# harp_behavior.net
KiCad netlist of a schematic drawn in EAGLE
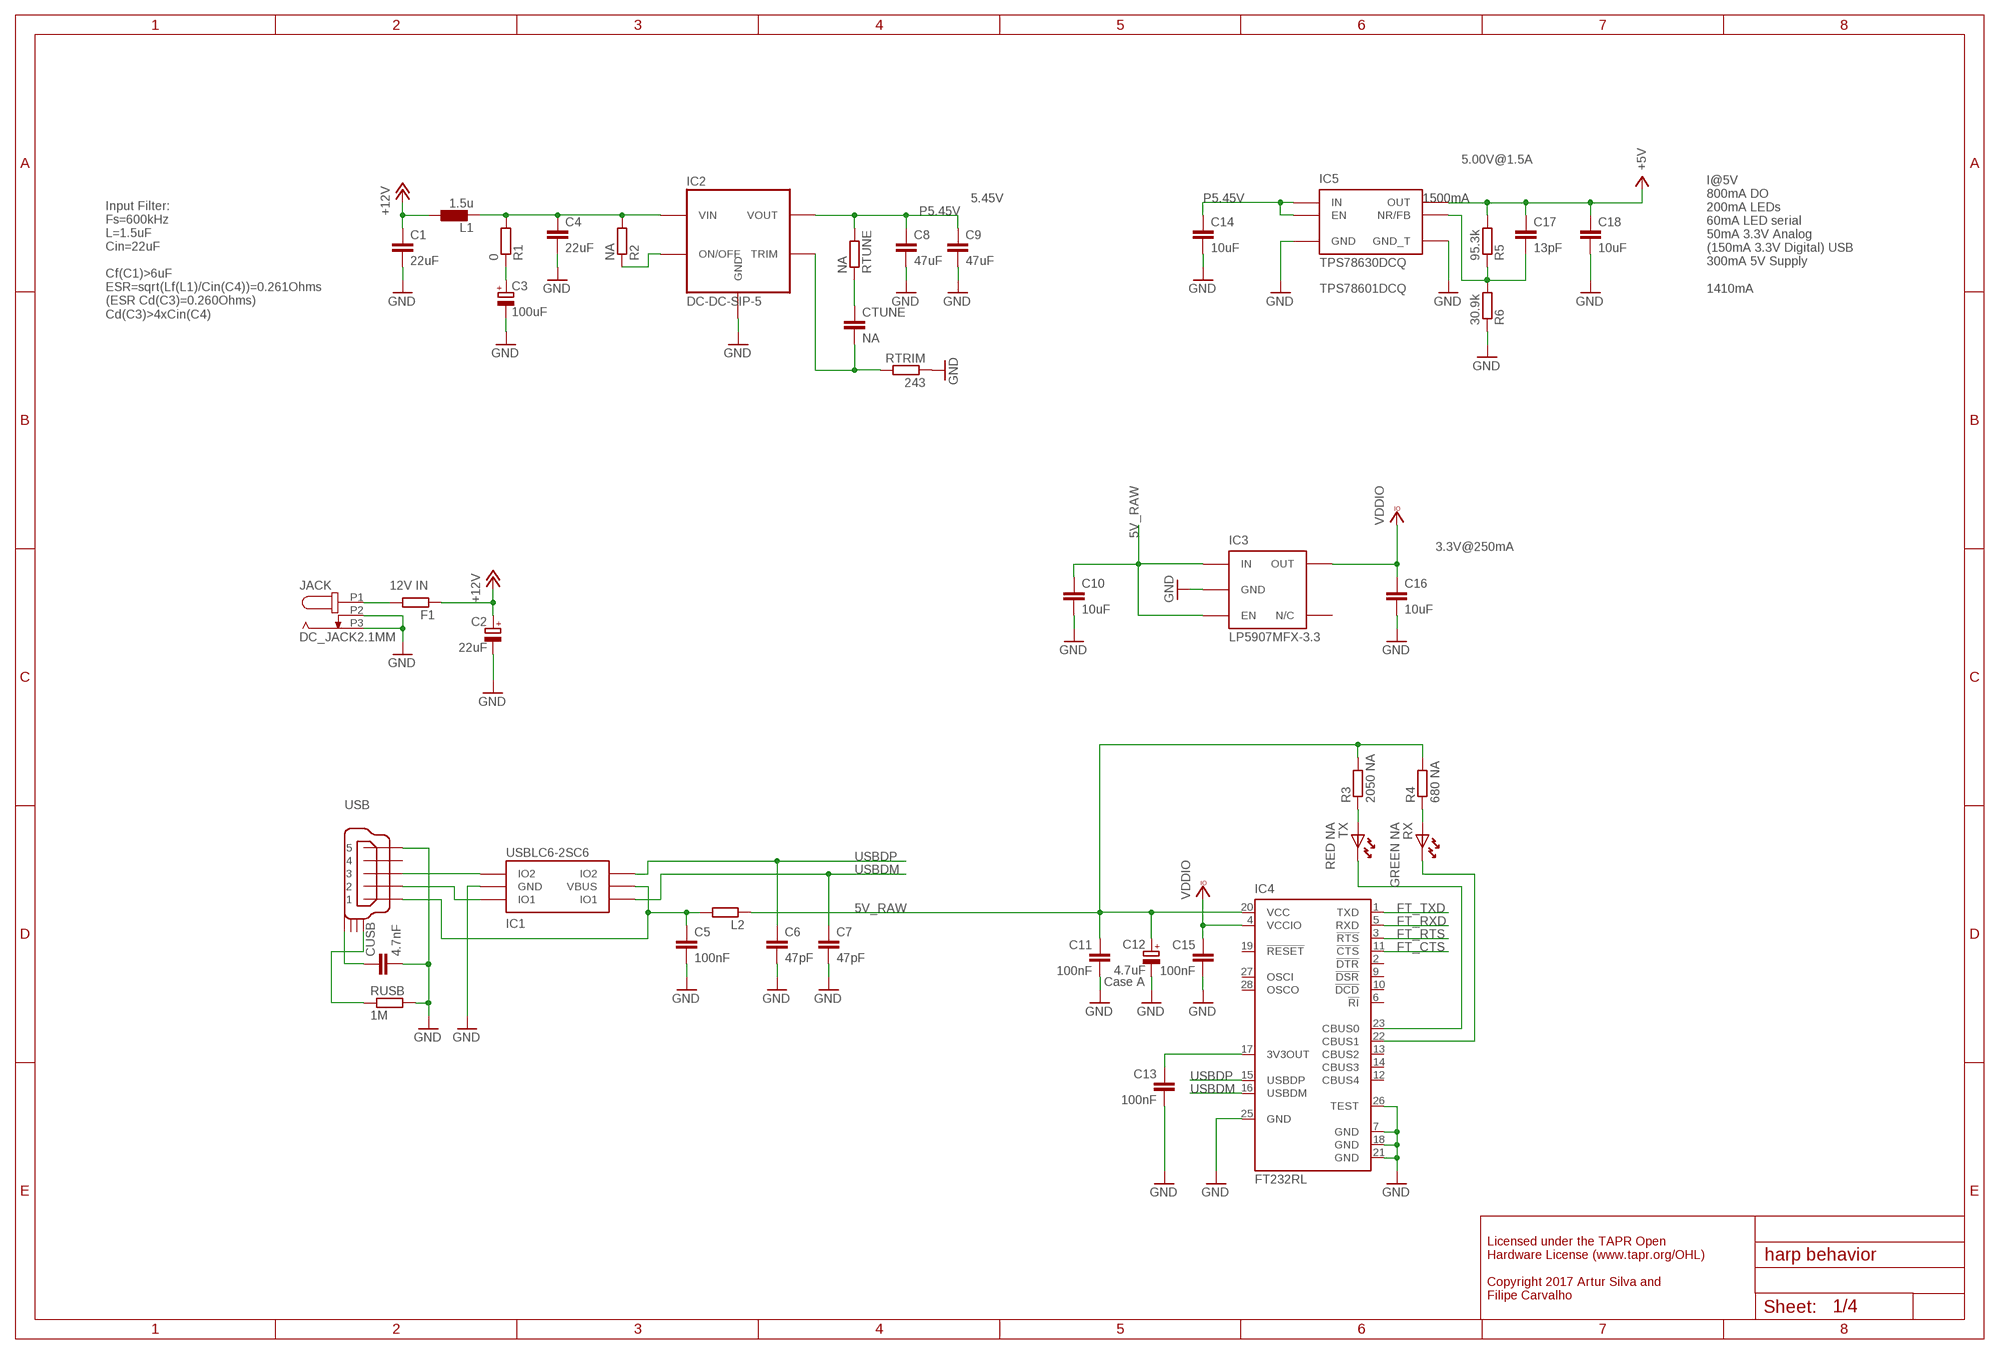
[diagram p0: schematic, sheet 1]
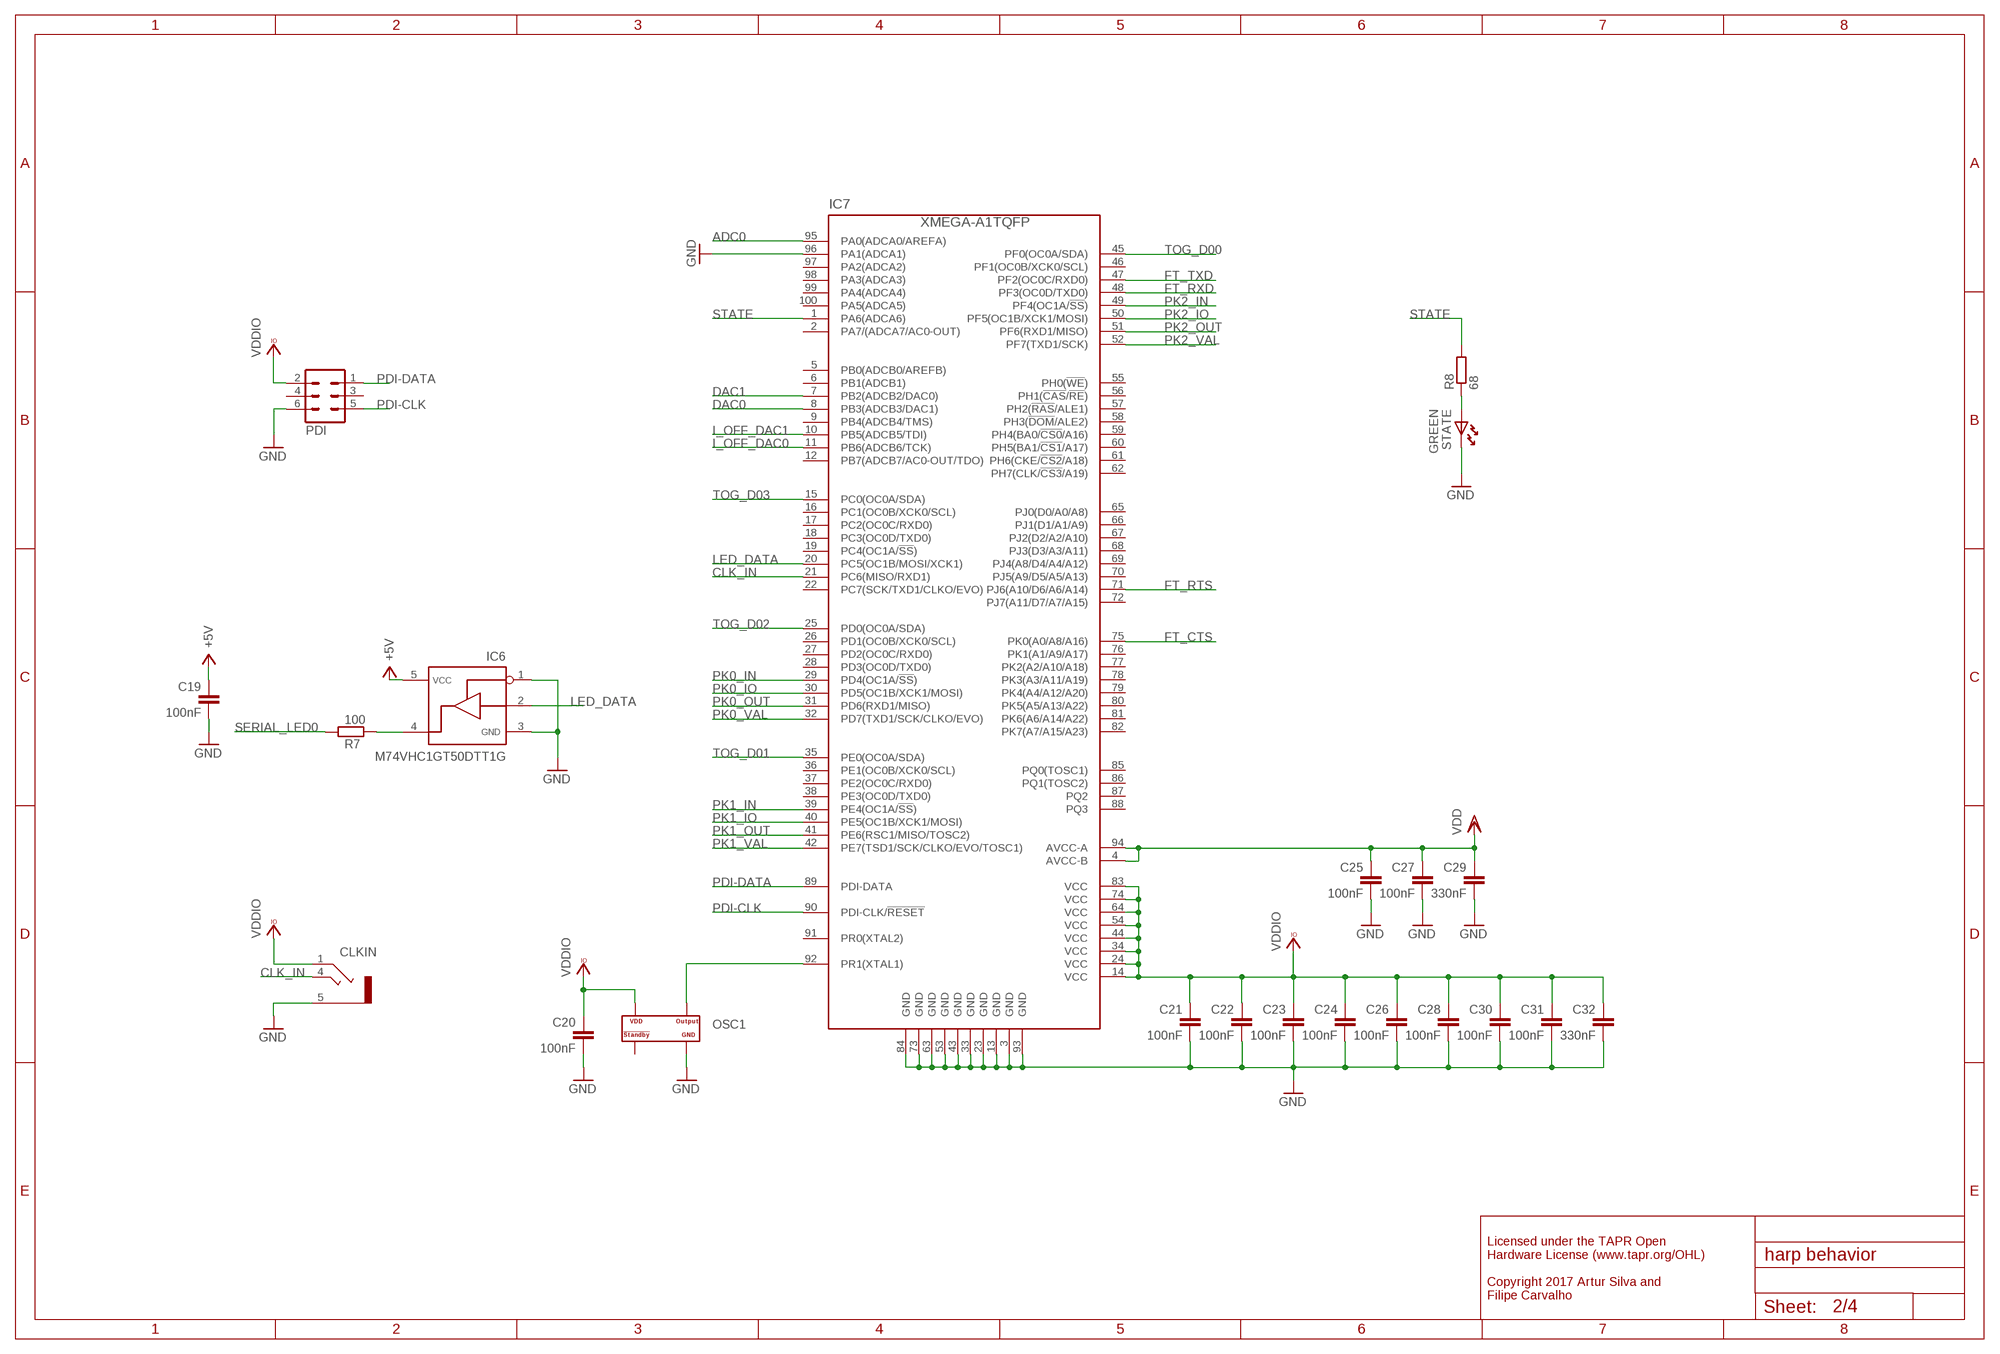
[diagram p1: schematic, sheet 2]
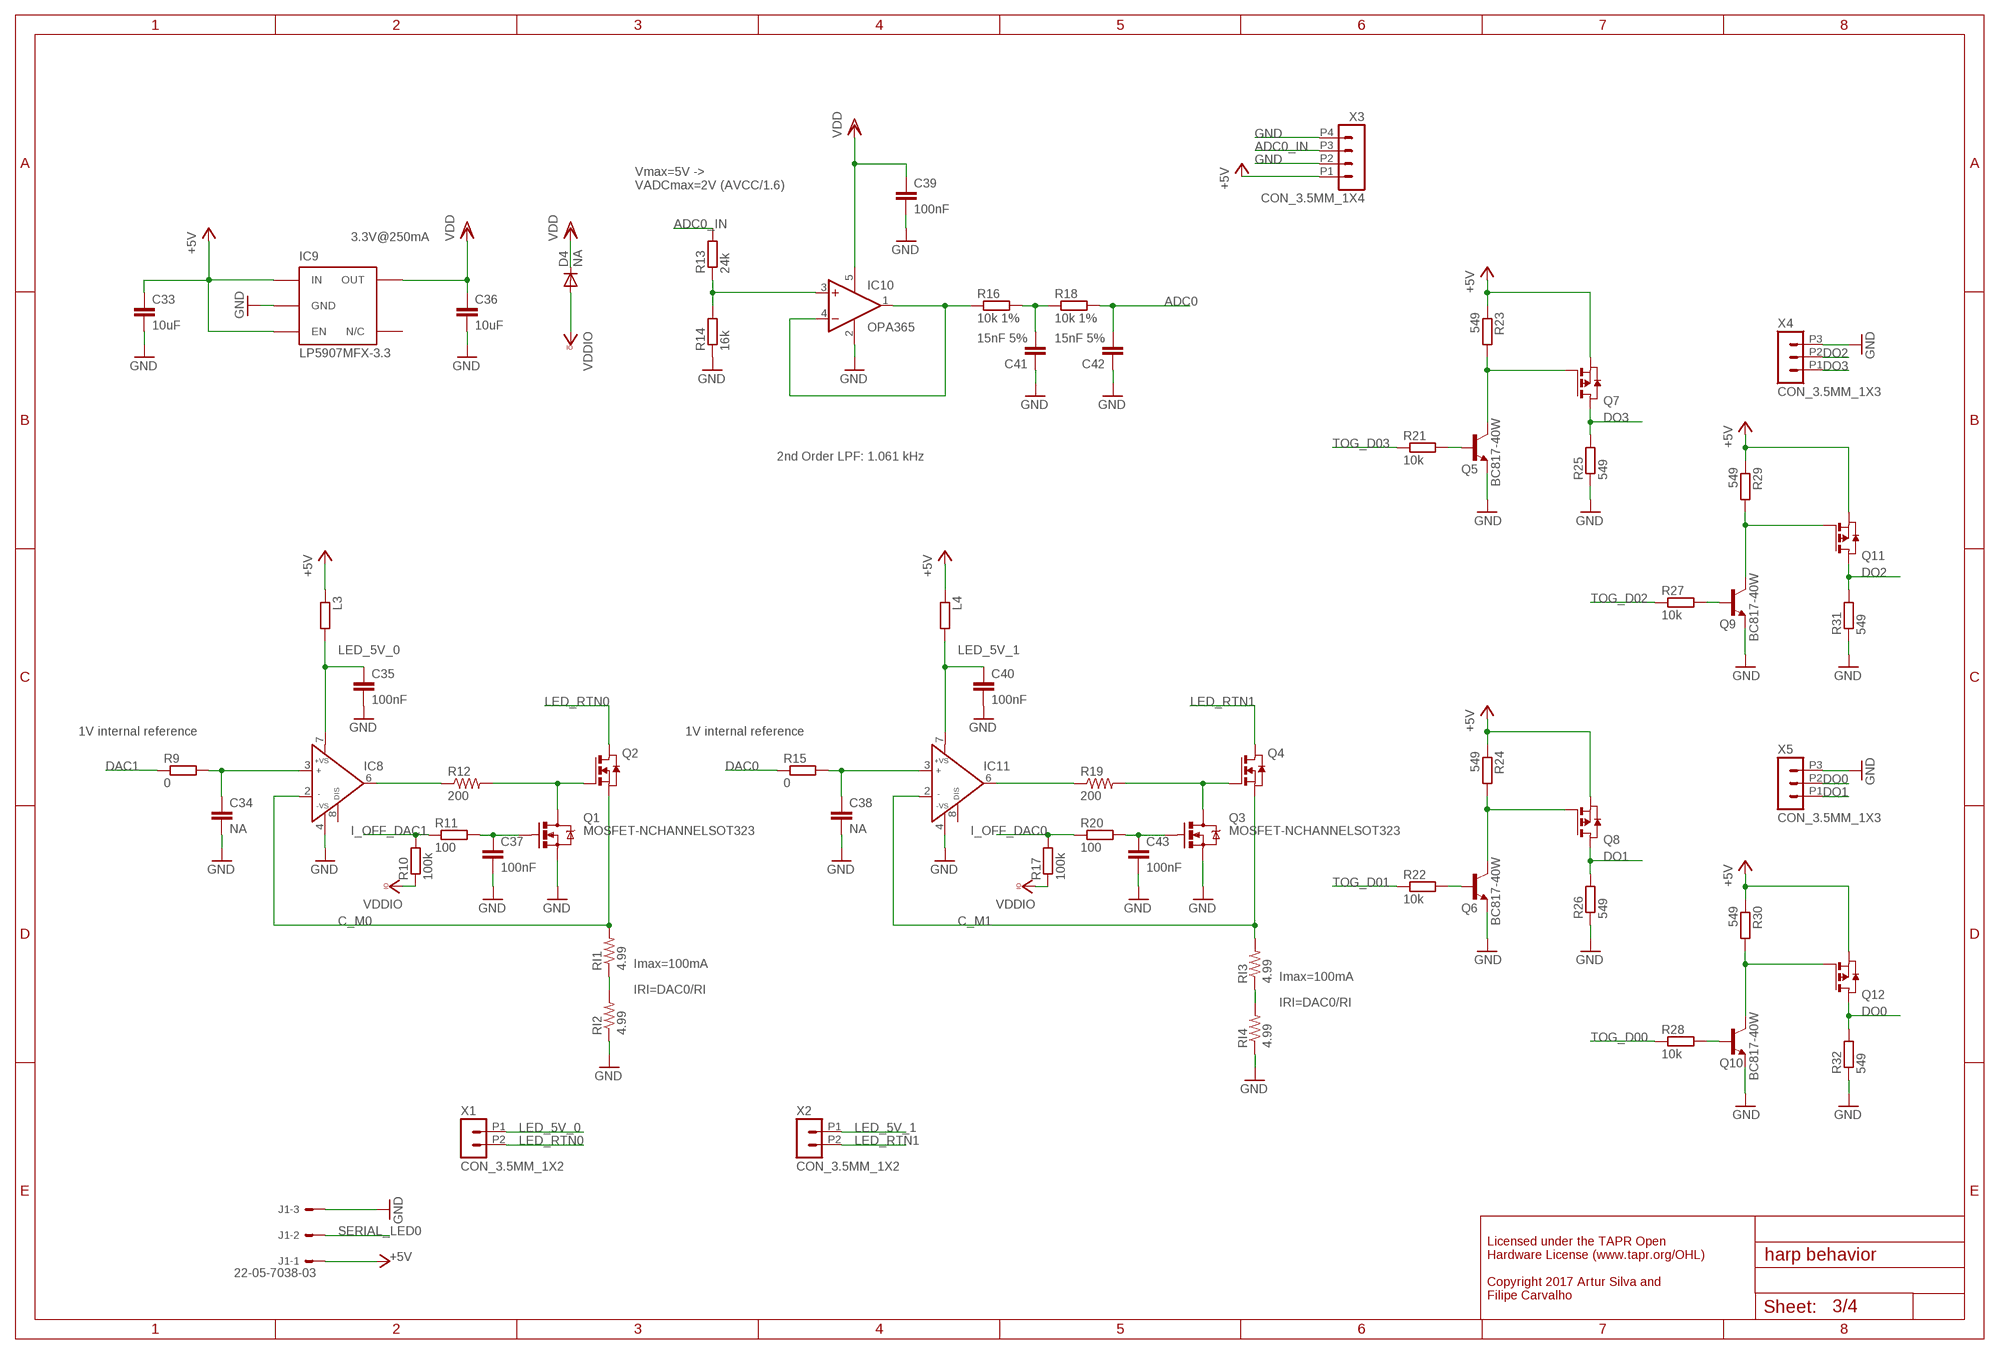
[diagram p2: schematic, sheet 3]
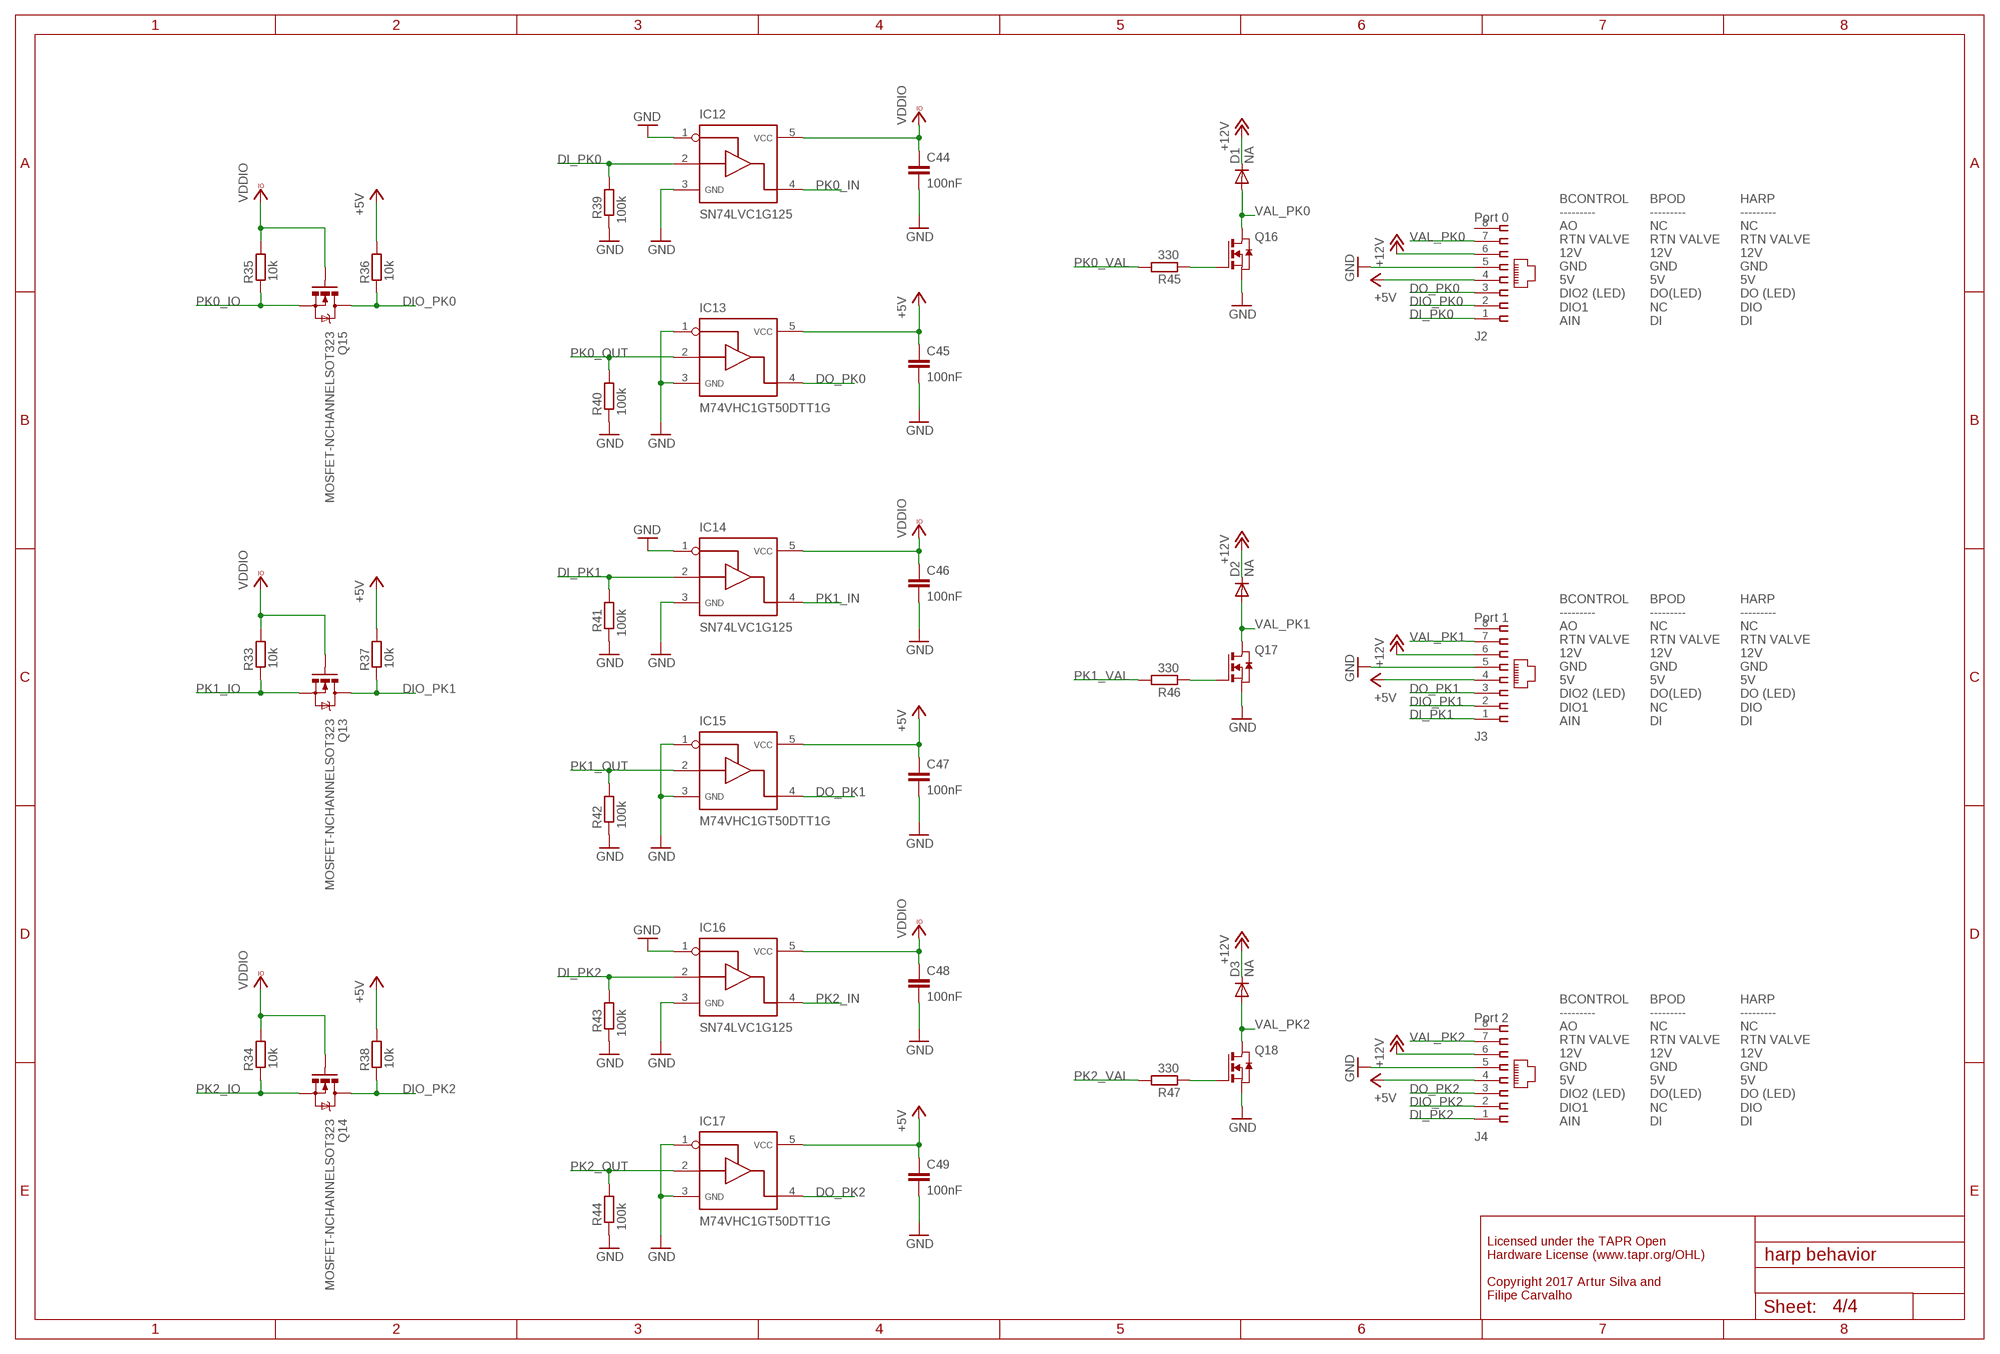
[diagram p3: schematic, sheet 4]

(export (version "E")
  (design (tool "Eeschema 10.0.6"))
  (components
    (comp (ref "C1")
      (value "22uF")
      (footprint "eagle-import:C1210")
      (libsource (lib "eagle-import") (part "C-EUC1210"))
    )
    (comp (ref "C2")
      (value "22uF")
      (footprint "eagle-import:CAP_100UF_HAND")
      (libsource (lib "eagle-import") (part "CAP_100UFHAND"))
    )
    (comp (ref "C3")
      (value "100uF")
      (footprint "eagle-import:PANASONIC_E")
      (libsource (lib "eagle-import") (part "CPOL-EUE"))
    )
    (comp (ref "C4")
      (value "22uF")
      (footprint "eagle-import:C1210")
      (libsource (lib "eagle-import") (part "C-EUC1210"))
    )
    (comp (ref "C5")
      (value "100nF")
      (footprint "eagle-import:C0402")
      (libsource (lib "eagle-import") (part "C-EUC0402"))
    )
    (comp (ref "C6")
      (value "47pF")
      (footprint "eagle-import:C0402")
      (libsource (lib "eagle-import") (part "C-EUC0402"))
    )
    (comp (ref "C7")
      (value "47pF")
      (footprint "eagle-import:C0402")
      (libsource (lib "eagle-import") (part "C-EUC0402"))
    )
    (comp (ref "C8")
      (value "47uF")
      (footprint "eagle-import:C1210")
      (libsource (lib "eagle-import") (part "C-EUC1210"))
    )
    (comp (ref "C9")
      (value "47uF")
      (footprint "eagle-import:C1210")
      (libsource (lib "eagle-import") (part "C-EUC1210"))
    )
    (comp (ref "C10")
      (value "10uF")
      (footprint "eagle-import:C0603")
      (libsource (lib "eagle-import") (part "C-EUC0603"))
    )
    (comp (ref "C11")
      (value "100nF")
      (footprint "eagle-import:C0402")
      (libsource (lib "eagle-import") (part "C-EUC0402"))
    )
    (comp (ref "C12")
      (value "4.7uF")
      (footprint "eagle-import:A_3216-18W")
      (libsource (lib "eagle-import") (part "CPOL-EUA/3216-18W"))
    )
    (comp (ref "C13")
      (value "100nF")
      (footprint "eagle-import:C0402")
      (libsource (lib "eagle-import") (part "C-EUC0402"))
    )
    (comp (ref "C14")
      (value "10uF")
      (footprint "eagle-import:C0603")
      (libsource (lib "eagle-import") (part "C-EUC0603"))
    )
    (comp (ref "C15")
      (value "100nF")
      (footprint "eagle-import:C0402")
      (libsource (lib "eagle-import") (part "C-EUC0402"))
    )
    (comp (ref "C16")
      (value "10uF")
      (footprint "eagle-import:C0603")
      (libsource (lib "eagle-import") (part "C-EUC0603"))
    )
    (comp (ref "C17")
      (value "13pF")
      (footprint "eagle-import:C0402")
      (libsource (lib "eagle-import") (part "C-EUC0402"))
    )
    (comp (ref "C18")
      (value "10uF")
      (footprint "eagle-import:C0603")
      (libsource (lib "eagle-import") (part "C-EUC0603"))
    )
    (comp (ref "CTUNE")
      (value "NA")
      (footprint "eagle-import:C0402")
      (libsource (lib "eagle-import") (part "C-EUC0402"))
    )
    (comp (ref "CUSB")
      (value "4.7nF")
      (footprint "eagle-import:C0402")
      (libsource (lib "eagle-import") (part "C-EUC0402"))
    )
    (comp (ref "F1")
      (value "1A FB")
      (footprint "eagle-import:R0603")
      (libsource (lib "eagle-import") (part "R-EU_R0603"))
    )
    (comp (ref "IC1")
      (value "USBLC6-2SC6")
      (footprint "eagle-import:SOT23-6L")
      (libsource (lib "eagle-import") (part "USBLC6-2"))
    )
    (comp (ref "IC2")
      (value "DC-DC-SIP-5")
      (footprint "eagle-import:SIP-5")
      (libsource (lib "eagle-import") (part "DC-DC-SIP-5"))
    )
    (comp (ref "IC3")
      (value "LP5907MFX-3.3")
      (footprint "eagle-import:TSOT23-5")
      (libsource (lib "eagle-import") (part "TLV700XX"))
    )
    (comp (ref "IC4")
      (value "FT232RL")
      (footprint "eagle-import:SSOP28")
      (libsource (lib "eagle-import") (part "FT232RL"))
    )
    (comp (ref "IC5")
      (value "TPS78630DCQ")
      (footprint "eagle-import:SOT223-6")
      (libsource (lib "eagle-import") (part "TPS795XX"))
    )
    (comp (ref "JACK")
      (value "DC_JACK2.1MM")
      (footprint "eagle-import:DC_POWER_INPUT_2.1MM")
      (libsource (lib "eagle-import") (part "DC_JACK2.1MM"))
    )
    (comp (ref "L1")
      (value "1.5u")
      (footprint "eagle-import:IND_LPS4012")
      (libsource (lib "eagle-import") (part "INDLPS4012"))
    )
    (comp (ref "L2")
      (value "???")
      (footprint "eagle-import:R0805")
      (libsource (lib "eagle-import") (part "R-EU_R0805"))
    )
    (comp (ref "R1")
      (value "0")
      (footprint "eagle-import:R0402")
      (libsource (lib "eagle-import") (part "R-EU_R0402"))
    )
    (comp (ref "R2")
      (value "NA")
      (footprint "eagle-import:R0402")
      (libsource (lib "eagle-import") (part "R-EU_R0402"))
    )
    (comp (ref "R3")
      (value "2050 NA")
      (footprint "eagle-import:R0402")
      (libsource (lib "eagle-import") (part "R-EU_R0402"))
    )
    (comp (ref "R4")
      (value "680 NA")
      (footprint "eagle-import:R0402")
      (libsource (lib "eagle-import") (part "R-EU_R0402"))
    )
    (comp (ref "R5")
      (value "95.3k")
      (footprint "eagle-import:R0402")
      (libsource (lib "eagle-import") (part "R-EU_R0402"))
    )
    (comp (ref "R6")
      (value "30.9k")
      (footprint "eagle-import:R0402")
      (libsource (lib "eagle-import") (part "R-EU_R0402"))
    )
    (comp (ref "RTRIM")
      (value "243")
      (footprint "eagle-import:R0402")
      (libsource (lib "eagle-import") (part "R-EU_R0402"))
    )
    (comp (ref "RTUNE")
      (value "NA")
      (footprint "eagle-import:R0402")
      (libsource (lib "eagle-import") (part "R-EU_R0402"))
    )
    (comp (ref "RUSB")
      (value "1M")
      (footprint "eagle-import:R0402")
      (libsource (lib "eagle-import") (part "R-EU_R0402"))
    )
    (comp (ref "RX")
      (value "GREEN NA")
      (footprint "eagle-import:LED_HAND")
      (libsource (lib "eagle-import") (part "LEDHAND"))
    )
    (comp (ref "TX")
      (value "RED NA")
      (footprint "eagle-import:LED_HAND")
      (libsource (lib "eagle-import") (part "LEDHAND"))
    )
    (comp (ref "USB")
      (value "USB_MINI_B")
      (footprint "eagle-import:240-0002-1")
      (libsource (lib "eagle-import") (part "USB_MINI_B"))
    )
    (comp (ref "C19")
      (value "100nF")
      (footprint "eagle-import:C0402")
      (libsource (lib "eagle-import") (part "C-EUC0402"))
    )
    (comp (ref "C20")
      (value "100nF")
      (footprint "eagle-import:C0402")
      (libsource (lib "eagle-import") (part "C-EUC0402"))
    )
    (comp (ref "C21")
      (value "100nF")
      (footprint "eagle-import:C0402")
      (libsource (lib "eagle-import") (part "C-EUC0402"))
    )
    (comp (ref "C22")
      (value "100nF")
      (footprint "eagle-import:C0402")
      (libsource (lib "eagle-import") (part "C-EUC0402"))
    )
    (comp (ref "C23")
      (value "100nF")
      (footprint "eagle-import:C0402")
      (libsource (lib "eagle-import") (part "C-EUC0402"))
    )
    (comp (ref "C24")
      (value "100nF")
      (footprint "eagle-import:C0402")
      (libsource (lib "eagle-import") (part "C-EUC0402"))
    )
    (comp (ref "C25")
      (value "100nF")
      (footprint "eagle-import:C0402")
      (libsource (lib "eagle-import") (part "C-EUC0402"))
    )
    (comp (ref "C26")
      (value "100nF")
      (footprint "eagle-import:C0402")
      (libsource (lib "eagle-import") (part "C-EUC0402"))
    )
    (comp (ref "C27")
      (value "100nF")
      (footprint "eagle-import:C0402")
      (libsource (lib "eagle-import") (part "C-EUC0402"))
    )
    (comp (ref "C28")
      (value "100nF")
      (footprint "eagle-import:C0402")
      (libsource (lib "eagle-import") (part "C-EUC0402"))
    )
    (comp (ref "C29")
      (value "330nF")
      (footprint "eagle-import:C0402")
      (libsource (lib "eagle-import") (part "C-EUC0402"))
    )
    (comp (ref "C30")
      (value "100nF")
      (footprint "eagle-import:C0402")
      (libsource (lib "eagle-import") (part "C-EUC0402"))
    )
    (comp (ref "C31")
      (value "100nF")
      (footprint "eagle-import:C0402")
      (libsource (lib "eagle-import") (part "C-EUC0402"))
    )
    (comp (ref "C32")
      (value "330nF")
      (footprint "eagle-import:C0402")
      (libsource (lib "eagle-import") (part "C-EUC0402"))
    )
    (comp (ref "CLKIN")
      (value "STEREO_JACK")
      (footprint "eagle-import:35RASMT2BHNTRX")
      (libsource (lib "eagle-import") (part "STEREO_JACK"))
    )
    (comp (ref "IC6")
      (value "M74VHC1GT50DTT1G")
      (footprint "eagle-import:SOT23-5")
      (libsource (lib "eagle-import") (part "SN74LVC1G125"))
    )
    (comp (ref "IC7")
      (value "XMEGA-A1TQFP")
      (footprint "eagle-import:TQFP100")
      (libsource (lib "eagle-import") (part "XMEGA-A1TQFP"))
    )
    (comp (ref "OSC1")
      (value "OSCILLATOR")
      (footprint "eagle-import:OSCILLATOR_3.2X2.5")
      (libsource (lib "eagle-import") (part "OSCILLATOR"))
    )
    (comp (ref "PDI")
      (value "MA03-2")
      (footprint "eagle-import:MA03-2")
      (libsource (lib "eagle-import") (part "MA03-2"))
    )
    (comp (ref "R7")
      (value "100")
      (footprint "eagle-import:R0402")
      (libsource (lib "eagle-import") (part "R-EU_R0402"))
    )
    (comp (ref "R8")
      (value "68")
      (footprint "eagle-import:R0402")
      (libsource (lib "eagle-import") (part "R-EU_R0402"))
    )
    (comp (ref "STATE")
      (value "GREEN")
      (footprint "eagle-import:LED_HAND")
      (libsource (lib "eagle-import") (part "LEDHAND"))
    )
    (comp (ref "C44")
      (value "100nF")
      (footprint "eagle-import:C0402")
      (libsource (lib "eagle-import") (part "C-EUC0402"))
    )
    (comp (ref "C45")
      (value "100nF")
      (footprint "eagle-import:C0402")
      (libsource (lib "eagle-import") (part "C-EUC0402"))
    )
    (comp (ref "C46")
      (value "100nF")
      (footprint "eagle-import:C0402")
      (libsource (lib "eagle-import") (part "C-EUC0402"))
    )
    (comp (ref "C47")
      (value "100nF")
      (footprint "eagle-import:C0402")
      (libsource (lib "eagle-import") (part "C-EUC0402"))
    )
    (comp (ref "C48")
      (value "100nF")
      (footprint "eagle-import:C0402")
      (libsource (lib "eagle-import") (part "C-EUC0402"))
    )
    (comp (ref "C49")
      (value "100nF")
      (footprint "eagle-import:C0402")
      (libsource (lib "eagle-import") (part "C-EUC0402"))
    )
    (comp (ref "D1")
      (value "NA")
      (footprint "eagle-import:SOD323-R")
      (libsource (lib "eagle-import") (part "DIODE-SOD323-R"))
    )
    (comp (ref "D2")
      (value "NA")
      (footprint "eagle-import:SOD323-R")
      (libsource (lib "eagle-import") (part "DIODE-SOD323-R"))
    )
    (comp (ref "D3")
      (value "NA")
      (footprint "eagle-import:SOD323-R")
      (libsource (lib "eagle-import") (part "DIODE-SOD323-R"))
    )
    (comp (ref "IC12")
      (value "SN74LVC1G125")
      (footprint "eagle-import:SOT23-5")
      (libsource (lib "eagle-import") (part "SN74LVC1G125"))
    )
    (comp (ref "IC13")
      (value "M74VHC1GT50DTT1G")
      (footprint "eagle-import:SOT23-5")
      (libsource (lib "eagle-import") (part "SN74LVC1G125"))
    )
    (comp (ref "IC14")
      (value "SN74LVC1G125")
      (footprint "eagle-import:SOT23-5")
      (libsource (lib "eagle-import") (part "SN74LVC1G125"))
    )
    (comp (ref "IC15")
      (value "M74VHC1GT50DTT1G")
      (footprint "eagle-import:SOT23-5")
      (libsource (lib "eagle-import") (part "SN74LVC1G125"))
    )
    (comp (ref "IC16")
      (value "SN74LVC1G125")
      (footprint "eagle-import:SOT23-5")
      (libsource (lib "eagle-import") (part "SN74LVC1G125"))
    )
    (comp (ref "IC17")
      (value "M74VHC1GT50DTT1G")
      (footprint "eagle-import:SOT23-5")
      (libsource (lib "eagle-import") (part "SN74LVC1G125"))
    )
    (comp (ref "J2")
      (value "Port 0")
      (footprint "eagle-import:520426-4")
      (libsource (lib "eagle-import") (part "520426-4"))
    )
    (comp (ref "J3")
      (value "Port 1")
      (footprint "eagle-import:520426-4")
      (libsource (lib "eagle-import") (part "520426-4"))
    )
    (comp (ref "J4")
      (value "Port 2")
      (footprint "eagle-import:520426-4")
      (libsource (lib "eagle-import") (part "520426-4"))
    )
    (comp (ref "Q13")
      (value "MOSFET-NCHANNELSOT323")
      (footprint "eagle-import:SOT323")
      (libsource (lib "eagle-import") (part "MOSFET-NCHANNELSOT323"))
    )
    (comp (ref "Q14")
      (value "MOSFET-NCHANNELSOT323")
      (footprint "eagle-import:SOT323")
      (libsource (lib "eagle-import") (part "MOSFET-NCHANNELSOT323"))
    )
    (comp (ref "Q15")
      (value "MOSFET-NCHANNELSOT323")
      (footprint "eagle-import:SOT323")
      (libsource (lib "eagle-import") (part "MOSFET-NCHANNELSOT323"))
    )
    (comp (ref "Q16")
      (value "NMOSSOT223")
      (footprint "eagle-import:SOT223")
      (libsource (lib "eagle-import") (part "NMOSSOT223"))
    )
    (comp (ref "Q17")
      (value "NMOSSOT223")
      (footprint "eagle-import:SOT223")
      (libsource (lib "eagle-import") (part "NMOSSOT223"))
    )
    (comp (ref "Q18")
      (value "NMOSSOT223")
      (footprint "eagle-import:SOT223")
      (libsource (lib "eagle-import") (part "NMOSSOT223"))
    )
    (comp (ref "R33")
      (value "10k")
      (footprint "eagle-import:R0402")
      (libsource (lib "eagle-import") (part "R-EU_R0402"))
    )
    (comp (ref "R34")
      (value "10k")
      (footprint "eagle-import:R0402")
      (libsource (lib "eagle-import") (part "R-EU_R0402"))
    )
    (comp (ref "R35")
      (value "10k")
      (footprint "eagle-import:R0402")
      (libsource (lib "eagle-import") (part "R-EU_R0402"))
    )
    (comp (ref "R36")
      (value "10k")
      (footprint "eagle-import:R0402")
      (libsource (lib "eagle-import") (part "R-EU_R0402"))
    )
    (comp (ref "R37")
      (value "10k")
      (footprint "eagle-import:R0402")
      (libsource (lib "eagle-import") (part "R-EU_R0402"))
    )
    (comp (ref "R38")
      (value "10k")
      (footprint "eagle-import:R0402")
      (libsource (lib "eagle-import") (part "R-EU_R0402"))
    )
    (comp (ref "R39")
      (value "100k")
      (footprint "eagle-import:R0402")
      (libsource (lib "eagle-import") (part "R-EU_R0402"))
    )
    (comp (ref "R40")
      (value "100k")
      (footprint "eagle-import:R0402")
      (libsource (lib "eagle-import") (part "R-EU_R0402"))
    )
    (comp (ref "R41")
      (value "100k")
      (footprint "eagle-import:R0402")
      (libsource (lib "eagle-import") (part "R-EU_R0402"))
    )
    (comp (ref "R42")
      (value "100k")
      (footprint "eagle-import:R0402")
      (libsource (lib "eagle-import") (part "R-EU_R0402"))
    )
    (comp (ref "R43")
      (value "100k")
      (footprint "eagle-import:R0402")
      (libsource (lib "eagle-import") (part "R-EU_R0402"))
    )
    (comp (ref "R44")
      (value "100k")
      (footprint "eagle-import:R0402")
      (libsource (lib "eagle-import") (part "R-EU_R0402"))
    )
    (comp (ref "R45")
      (value "330")
      (footprint "eagle-import:R0402")
      (libsource (lib "eagle-import") (part "R-EU_R0402"))
    )
    (comp (ref "R46")
      (value "330")
      (footprint "eagle-import:R0402")
      (libsource (lib "eagle-import") (part "R-EU_R0402"))
    )
    (comp (ref "R47")
      (value "330")
      (footprint "eagle-import:R0402")
      (libsource (lib "eagle-import") (part "R-EU_R0402"))
    )
    (comp (ref "C33")
      (value "10uF")
      (footprint "eagle-import:C0603")
      (libsource (lib "eagle-import") (part "C-EUC0603"))
    )
    (comp (ref "C34")
      (value "NA")
      (footprint "eagle-import:C0402")
      (libsource (lib "eagle-import") (part "C-EUC0402"))
    )
    (comp (ref "C35")
      (value "100nF")
      (footprint "eagle-import:C0402")
      (libsource (lib "eagle-import") (part "C-EUC0402"))
    )
    (comp (ref "C36")
      (value "10uF")
      (footprint "eagle-import:C0603")
      (libsource (lib "eagle-import") (part "C-EUC0603"))
    )
    (comp (ref "C37")
      (value "100nF")
      (footprint "eagle-import:C0402")
      (libsource (lib "eagle-import") (part "C-EUC0402"))
    )
    (comp (ref "C38")
      (value "NA")
      (footprint "eagle-import:C0402")
      (libsource (lib "eagle-import") (part "C-EUC0402"))
    )
    (comp (ref "C39")
      (value "100nF")
      (footprint "eagle-import:C0402")
      (libsource (lib "eagle-import") (part "C-EUC0402"))
    )
    (comp (ref "C40")
      (value "100nF")
      (footprint "eagle-import:C0402")
      (libsource (lib "eagle-import") (part "C-EUC0402"))
    )
    (comp (ref "C41")
      (value "15nF 5%")
      (footprint "eagle-import:C0402")
      (libsource (lib "eagle-import") (part "C-EUC0402"))
    )
    (comp (ref "C42")
      (value "15nF 5%")
      (footprint "eagle-import:C0402")
      (libsource (lib "eagle-import") (part "C-EUC0402"))
    )
    (comp (ref "C43")
      (value "100nF")
      (footprint "eagle-import:C0402")
      (libsource (lib "eagle-import") (part "C-EUC0402"))
    )
    (comp (ref "D4")
      (value "NA")
      (footprint "eagle-import:SOD323-R")
      (libsource (lib "eagle-import") (part "DIODE-SOD323-R"))
    )
    (comp (ref "IC8")
      (value "AD8041R")
      (footprint "eagle-import:SO8")
      (fields (field (name "MF") "ALTERA CORPORATION") (field (name "MPN") "AD8041ARZ"))
      (libsource (lib "eagle-import") (part "AD8041R"))
    )
    (comp (ref "IC9")
      (value "LP5907MFX-3.3")
      (footprint "eagle-import:TSOT23-5")
      (libsource (lib "eagle-import") (part "TLV700XX"))
    )
    (comp (ref "IC10")
      (value "OPA365")
      (footprint "eagle-import:SOT23-5")
      (libsource (lib "eagle-import") (part "OPA365"))
    )
    (comp (ref "IC11")
      (value "AD8041R")
      (footprint "eagle-import:SO8")
      (fields (field (name "MF") "ALTERA CORPORATION") (field (name "MPN") "AD8041ARZ"))
      (libsource (lib "eagle-import") (part "AD8041R"))
    )
    (comp (ref "J1")
      (value "22-05-7038-03")
      (footprint "eagle-import:7395-03")
      (libsource (lib "eagle-import") (part "22-?-0305-7038"))
    )
    (comp (ref "L3")
      (value "600@100M")
      (footprint "eagle-import:R0805")
      (libsource (lib "eagle-import") (part "R-EU_R0805"))
    )
    (comp (ref "L4")
      (value "600@100M")
      (footprint "eagle-import:R0805")
      (libsource (lib "eagle-import") (part "R-EU_R0805"))
    )
    (comp (ref "Q1")
      (value "MOSFET-NCHANNELSOT323")
      (footprint "eagle-import:SOT323")
      (libsource (lib "eagle-import") (part "MOSFET-NCHANNELSOT323"))
    )
    (comp (ref "Q2")
      (value "NMOSSOT223")
      (footprint "eagle-import:SOT223")
      (libsource (lib "eagle-import") (part "NMOSSOT223"))
    )
    (comp (ref "Q3")
      (value "MOSFET-NCHANNELSOT323")
      (footprint "eagle-import:SOT323")
      (libsource (lib "eagle-import") (part "MOSFET-NCHANNELSOT323"))
    )
    (comp (ref "Q4")
      (value "NMOSSOT223")
      (footprint "eagle-import:SOT223")
      (libsource (lib "eagle-import") (part "NMOSSOT223"))
    )
    (comp (ref "Q5")
      (value "BC817-40W")
      (footprint "eagle-import:SOT323-BEC")
      (libsource (lib "eagle-import") (part "BC817"))
    )
    (comp (ref "Q6")
      (value "BC817-40W")
      (footprint "eagle-import:SOT323-BEC")
      (libsource (lib "eagle-import") (part "BC817"))
    )
    (comp (ref "Q7")
      (value "PMOSSOT223")
      (footprint "eagle-import:SOT223")
      (libsource (lib "eagle-import") (part "PMOSSOT223"))
    )
    (comp (ref "Q8")
      (value "PMOSSOT223")
      (footprint "eagle-import:SOT223")
      (libsource (lib "eagle-import") (part "PMOSSOT223"))
    )
    (comp (ref "Q9")
      (value "BC817-40W")
      (footprint "eagle-import:SOT323-BEC")
      (libsource (lib "eagle-import") (part "BC817"))
    )
    (comp (ref "Q10")
      (value "BC817-40W")
      (footprint "eagle-import:SOT323-BEC")
      (libsource (lib "eagle-import") (part "BC817"))
    )
    (comp (ref "Q11")
      (value "PMOSSOT223")
      (footprint "eagle-import:SOT223")
      (libsource (lib "eagle-import") (part "PMOSSOT223"))
    )
    (comp (ref "Q12")
      (value "PMOSSOT223")
      (footprint "eagle-import:SOT223")
      (libsource (lib "eagle-import") (part "PMOSSOT223"))
    )
    (comp (ref "R9")
      (value "0")
      (footprint "eagle-import:R0402")
      (libsource (lib "eagle-import") (part "R-EU_R0402"))
    )
    (comp (ref "R10")
      (value "100k")
      (footprint "eagle-import:R0402")
      (libsource (lib "eagle-import") (part "R-EU_R0402"))
    )
    (comp (ref "R11")
      (value "100")
      (footprint "eagle-import:R0402")
      (libsource (lib "eagle-import") (part "R-EU_R0402"))
    )
    (comp (ref "R12")
      (value "200")
      (footprint "eagle-import:R1210")
      (libsource (lib "eagle-import") (part "R-US_R1210"))
    )
    (comp (ref "R13")
      (value "24k")
      (footprint "eagle-import:R0402")
      (libsource (lib "eagle-import") (part "R-EU_R0402"))
    )
    (comp (ref "R14")
      (value "16k")
      (footprint "eagle-import:R0402")
      (libsource (lib "eagle-import") (part "R-EU_R0402"))
    )
    (comp (ref "R15")
      (value "0")
      (footprint "eagle-import:R0402")
      (libsource (lib "eagle-import") (part "R-EU_R0402"))
    )
    (comp (ref "R16")
      (value "10k 1%")
      (footprint "eagle-import:R0402")
      (libsource (lib "eagle-import") (part "R-EU_R0402"))
    )
    (comp (ref "R17")
      (value "100k")
      (footprint "eagle-import:R0402")
      (libsource (lib "eagle-import") (part "R-EU_R0402"))
    )
    (comp (ref "R18")
      (value "10k 1%")
      (footprint "eagle-import:R0402")
      (libsource (lib "eagle-import") (part "R-EU_R0402"))
    )
    (comp (ref "R19")
      (value "200")
      (footprint "eagle-import:R1210")
      (libsource (lib "eagle-import") (part "R-US_R1210"))
    )
    (comp (ref "R20")
      (value "100")
      (footprint "eagle-import:R0402")
      (libsource (lib "eagle-import") (part "R-EU_R0402"))
    )
    (comp (ref "R21")
      (value "10k")
      (footprint "eagle-import:R0402")
      (libsource (lib "eagle-import") (part "R-EU_R0402"))
    )
    (comp (ref "R22")
      (value "10k")
      (footprint "eagle-import:R0402")
      (libsource (lib "eagle-import") (part "R-EU_R0402"))
    )
    (comp (ref "R23")
      (value "549")
      (footprint "eagle-import:R0805")
      (libsource (lib "eagle-import") (part "R-EU_R0805"))
    )
    (comp (ref "R24")
      (value "549")
      (footprint "eagle-import:R0805")
      (libsource (lib "eagle-import") (part "R-EU_R0805"))
    )
    (comp (ref "R25")
      (value "549")
      (footprint "eagle-import:R0805")
      (libsource (lib "eagle-import") (part "R-EU_R0805"))
    )
    (comp (ref "R26")
      (value "549")
      (footprint "eagle-import:R0805")
      (libsource (lib "eagle-import") (part "R-EU_R0805"))
    )
    (comp (ref "R27")
      (value "10k")
      (footprint "eagle-import:R0402")
      (libsource (lib "eagle-import") (part "R-EU_R0402"))
    )
    (comp (ref "R28")
      (value "10k")
      (footprint "eagle-import:R0402")
      (libsource (lib "eagle-import") (part "R-EU_R0402"))
    )
    (comp (ref "R29")
      (value "549")
      (footprint "eagle-import:R0805")
      (libsource (lib "eagle-import") (part "R-EU_R0805"))
    )
    (comp (ref "R30")
      (value "549")
      (footprint "eagle-import:R0805")
      (libsource (lib "eagle-import") (part "R-EU_R0805"))
    )
    (comp (ref "R31")
      (value "549")
      (footprint "eagle-import:R0805")
      (libsource (lib "eagle-import") (part "R-EU_R0805"))
    )
    (comp (ref "R32")
      (value "549")
      (footprint "eagle-import:R0805")
      (libsource (lib "eagle-import") (part "R-EU_R0805"))
    )
    (comp (ref "RI1")
      (value "4.99")
      (footprint "eagle-import:R2512")
      (libsource (lib "eagle-import") (part "R-US_R2512"))
    )
    (comp (ref "RI2")
      (value "4.99")
      (footprint "eagle-import:R2512")
      (libsource (lib "eagle-import") (part "R-US_R2512"))
    )
    (comp (ref "RI3")
      (value "4.99")
      (footprint "eagle-import:R2512")
      (libsource (lib "eagle-import") (part "R-US_R2512"))
    )
    (comp (ref "RI4")
      (value "4.99")
      (footprint "eagle-import:R2512")
      (libsource (lib "eagle-import") (part "R-US_R2512"))
    )
    (comp (ref "X1")
      (value "CON_3.5MM_1X2")
      (footprint "eagle-import:CON_3.5MM_1X2")
      (libsource (lib "eagle-import") (part "CON_3.5MM_1X2"))
    )
    (comp (ref "X2")
      (value "CON_3.5MM_1X2")
      (footprint "eagle-import:CON_3.5MM_1X2")
      (libsource (lib "eagle-import") (part "CON_3.5MM_1X2"))
    )
    (comp (ref "X3")
      (value "CON_3.5MM_1X4")
      (footprint "eagle-import:CON_3.5MM_1X4")
      (libsource (lib "eagle-import") (part "CON_3.5MM_1X4"))
    )
    (comp (ref "X4")
      (value "CON_3.5MM_1X3")
      (footprint "eagle-import:CON_3.5MM_1X3")
      (libsource (lib "eagle-import") (part "CON_3.5MM_1X3"))
    )
    (comp (ref "X5")
      (value "CON_3.5MM_1X3")
      (footprint "eagle-import:CON_3.5MM_1X3")
      (libsource (lib "eagle-import") (part "CON_3.5MM_1X3"))
    )
  )
  (nets
    (net (code "1") (name "+5V") (class "Default")
      (node (ref "C17") (pin "1") (pinfunction "1_1") (pintype "passive"))
      (node (ref "C18") (pin "1") (pinfunction "1_1") (pintype "passive"))
      (node (ref "C19") (pin "1") (pinfunction "1_1") (pintype "passive"))
      (node (ref "C33") (pin "1") (pinfunction "1_1") (pintype "passive"))
      (node (ref "C45") (pin "1") (pinfunction "1_1") (pintype "passive"))
      (node (ref "C47") (pin "1") (pinfunction "1_1") (pintype "passive"))
      (node (ref "C49") (pin "1") (pinfunction "1_1") (pintype "passive"))
      (node (ref "IC13") (pin "5") (pinfunction "P$5_5") (pintype "bidirectional"))
      (node (ref "IC15") (pin "5") (pinfunction "P$5_5") (pintype "bidirectional"))
      (node (ref "IC17") (pin "5") (pinfunction "P$5_5") (pintype "bidirectional"))
      (node (ref "IC5") (pin "P$4") (pinfunction "OUT_P$4") (pintype "bidirectional"))
      (node (ref "IC6") (pin "5") (pinfunction "P$5_5") (pintype "bidirectional"))
      (node (ref "IC9") (pin "1") (pinfunction "IN_1") (pintype "bidirectional"))
      (node (ref "IC9") (pin "3") (pinfunction "EN_3") (pintype "bidirectional"))
      (node (ref "J1") (pin "1") (pinfunction "S_1") (pintype "passive"))
      (node (ref "J2") (pin "4") (pinfunction "4_4") (pintype "passive"))
      (node (ref "J3") (pin "4") (pinfunction "4_4") (pintype "passive"))
      (node (ref "J4") (pin "4") (pinfunction "4_4") (pintype "passive"))
      (node (ref "L3") (pin "1") (pinfunction "1_1") (pintype "passive"))
      (node (ref "L4") (pin "1") (pinfunction "1_1") (pintype "passive"))
      (node (ref "Q11") (pin "3") (pinfunction "S_3") (pintype "passive"))
      (node (ref "Q12") (pin "3") (pinfunction "S_3") (pintype "passive"))
      (node (ref "Q7") (pin "3") (pinfunction "S_3") (pintype "passive"))
      (node (ref "Q8") (pin "3") (pinfunction "S_3") (pintype "passive"))
      (node (ref "R23") (pin "1") (pinfunction "1_1") (pintype "passive"))
      (node (ref "R24") (pin "1") (pinfunction "1_1") (pintype "passive"))
      (node (ref "R29") (pin "1") (pinfunction "1_1") (pintype "passive"))
      (node (ref "R30") (pin "1") (pinfunction "1_1") (pintype "passive"))
      (node (ref "R36") (pin "1") (pinfunction "1_1") (pintype "passive"))
      (node (ref "R37") (pin "1") (pinfunction "1_1") (pintype "passive"))
      (node (ref "R38") (pin "1") (pinfunction "1_1") (pintype "passive"))
      (node (ref "R5") (pin "2") (pinfunction "2_2") (pintype "passive"))
      (node (ref "X3") (pin "P1") (pinfunction "1_P1") (pintype "passive"))
    )
    (net (code "2") (name "+12V") (class "Default")
      (node (ref "C1") (pin "1") (pinfunction "1_1") (pintype "passive"))
      (node (ref "C2") (pin "+") (pinfunction "+_+") (pintype "passive"))
      (node (ref "D1") (pin "C") (pinfunction "C_C") (pintype "passive"))
      (node (ref "D2") (pin "C") (pinfunction "C_C") (pintype "passive"))
      (node (ref "D3") (pin "C") (pinfunction "C_C") (pintype "passive"))
      (node (ref "F1") (pin "1") (pinfunction "1_1") (pintype "passive"))
      (node (ref "J2") (pin "6") (pinfunction "6_6") (pintype "passive"))
      (node (ref "J3") (pin "6") (pinfunction "6_6") (pintype "passive"))
      (node (ref "J4") (pin "6") (pinfunction "6_6") (pintype "passive"))
      (node (ref "L1") (pin "1") (pinfunction "1_1") (pintype "passive"))
    )
    (net (code "3") (name "5V_RAW") (class "Default")
      (node (ref "C10") (pin "1") (pinfunction "1_1") (pintype "passive"))
      (node (ref "C11") (pin "1") (pinfunction "1_1") (pintype "passive"))
      (node (ref "C12") (pin "+") (pinfunction "+_+") (pintype "passive"))
      (node (ref "IC3") (pin "1") (pinfunction "IN_1") (pintype "bidirectional"))
      (node (ref "IC3") (pin "3") (pinfunction "EN_3") (pintype "bidirectional"))
      (node (ref "IC4") (pin "20") (pinfunction "VCC_20") (pintype "power_in"))
      (node (ref "L2") (pin "1") (pinfunction "1_1") (pintype "passive"))
      (node (ref "R3") (pin "2") (pinfunction "2_2") (pintype "passive"))
      (node (ref "R4") (pin "2") (pinfunction "2_2") (pintype "passive"))
    )
    (net (code "4") (name "ADC0") (class "Default")
      (node (ref "C42") (pin "2") (pinfunction "2_2") (pintype "passive"))
      (node (ref "IC7") (pin "95") (pinfunction "PA0(ADCA0/AREFA)_95") (pintype "bidirectional"))
      (node (ref "R18") (pin "2") (pinfunction "2_2") (pintype "passive"))
    )
    (net (code "5") (name "ADC0_IN") (class "Default")
      (node (ref "R13") (pin "2") (pinfunction "2_2") (pintype "passive"))
      (node (ref "X3") (pin "P3") (pinfunction "3_P3") (pintype "passive"))
    )
    (net (code "6") (name "CLK_IN") (class "Default")
      (node (ref "CLKIN") (pin "4") (pinfunction "4_4") (pintype "passive"))
      (node (ref "IC7") (pin "21") (pinfunction "PC6(MISO/RXD1)_21") (pintype "bidirectional"))
    )
    (net (code "7") (name "C_M0") (class "Default")
      (node (ref "IC8") (pin "2") (pinfunction "IN-_2") (pintype "input"))
      (node (ref "Q2") (pin "3") (pinfunction "S_3") (pintype "passive"))
      (node (ref "RI1") (pin "2") (pinfunction "2_2") (pintype "passive"))
    )
    (net (code "8") (name "C_M1") (class "Default")
      (node (ref "IC11") (pin "2") (pinfunction "IN-_2") (pintype "input"))
      (node (ref "Q4") (pin "3") (pinfunction "S_3") (pintype "passive"))
      (node (ref "RI3") (pin "2") (pinfunction "2_2") (pintype "passive"))
    )
    (net (code "9") (name "DAC0") (class "Default")
      (node (ref "IC7") (pin "8") (pinfunction "PB3(ADCB3/DAC1)_8") (pintype "bidirectional"))
      (node (ref "R15") (pin "1") (pinfunction "1_1") (pintype "passive"))
    )
    (net (code "10") (name "DAC1") (class "Default")
      (node (ref "IC7") (pin "7") (pinfunction "PB2(ADCB2/DAC0)_7") (pintype "bidirectional"))
      (node (ref "R9") (pin "1") (pinfunction "1_1") (pintype "passive"))
    )
    (net (code "11") (name "DIO_PK0") (class "Default")
      (node (ref "J2") (pin "2") (pinfunction "2_2") (pintype "passive"))
      (node (ref "Q15") (pin "3") (pinfunction "D_3") (pintype "passive"))
      (node (ref "R36") (pin "2") (pinfunction "2_2") (pintype "passive"))
    )
    (net (code "12") (name "DIO_PK1") (class "Default")
      (node (ref "J3") (pin "2") (pinfunction "2_2") (pintype "passive"))
      (node (ref "Q13") (pin "3") (pinfunction "D_3") (pintype "passive"))
      (node (ref "R37") (pin "2") (pinfunction "2_2") (pintype "passive"))
    )
    (net (code "13") (name "DIO_PK2") (class "Default")
      (node (ref "J4") (pin "2") (pinfunction "2_2") (pintype "passive"))
      (node (ref "Q14") (pin "3") (pinfunction "D_3") (pintype "passive"))
      (node (ref "R38") (pin "2") (pinfunction "2_2") (pintype "passive"))
    )
    (net (code "14") (name "DI_PK0") (class "Default")
      (node (ref "IC12") (pin "2") (pinfunction "P$2_2") (pintype "bidirectional"))
      (node (ref "J2") (pin "1") (pinfunction "1_1") (pintype "passive"))
      (node (ref "R39") (pin "1") (pinfunction "1_1") (pintype "passive"))
    )
    (net (code "15") (name "DI_PK1") (class "Default")
      (node (ref "IC14") (pin "2") (pinfunction "P$2_2") (pintype "bidirectional"))
      (node (ref "J3") (pin "1") (pinfunction "1_1") (pintype "passive"))
      (node (ref "R41") (pin "1") (pinfunction "1_1") (pintype "passive"))
    )
    (net (code "16") (name "DI_PK2") (class "Default")
      (node (ref "IC16") (pin "2") (pinfunction "P$2_2") (pintype "bidirectional"))
      (node (ref "J4") (pin "1") (pinfunction "1_1") (pintype "passive"))
      (node (ref "R43") (pin "1") (pinfunction "1_1") (pintype "passive"))
    )
    (net (code "17") (name "DO0") (class "Default")
      (node (ref "Q12") (pin "2") (pinfunction "D_2") (pintype "passive"))
      (node (ref "Q12") (pin "4") (pinfunction "D_4") (pintype "passive"))
      (node (ref "R32") (pin "2") (pinfunction "2_2") (pintype "passive"))
      (node (ref "X5") (pin "P2") (pinfunction "2_P2") (pintype "passive"))
    )
    (net (code "18") (name "DO1") (class "Default")
      (node (ref "Q8") (pin "2") (pinfunction "D_2") (pintype "passive"))
      (node (ref "Q8") (pin "4") (pinfunction "D_4") (pintype "passive"))
      (node (ref "R26") (pin "2") (pinfunction "2_2") (pintype "passive"))
      (node (ref "X5") (pin "P1") (pinfunction "1_P1") (pintype "passive"))
    )
    (net (code "19") (name "DO2") (class "Default")
      (node (ref "Q11") (pin "2") (pinfunction "D_2") (pintype "passive"))
      (node (ref "Q11") (pin "4") (pinfunction "D_4") (pintype "passive"))
      (node (ref "R31") (pin "2") (pinfunction "2_2") (pintype "passive"))
      (node (ref "X4") (pin "P2") (pinfunction "2_P2") (pintype "passive"))
    )
    (net (code "20") (name "DO3") (class "Default")
      (node (ref "Q7") (pin "2") (pinfunction "D_2") (pintype "passive"))
      (node (ref "Q7") (pin "4") (pinfunction "D_4") (pintype "passive"))
      (node (ref "R25") (pin "2") (pinfunction "2_2") (pintype "passive"))
      (node (ref "X4") (pin "P1") (pinfunction "1_P1") (pintype "passive"))
    )
    (net (code "21") (name "DO_PK0") (class "Default")
      (node (ref "IC13") (pin "4") (pinfunction "P$4_4") (pintype "bidirectional"))
      (node (ref "J2") (pin "3") (pinfunction "3_3") (pintype "passive"))
    )
    (net (code "22") (name "DO_PK1") (class "Default")
      (node (ref "IC15") (pin "4") (pinfunction "P$4_4") (pintype "bidirectional"))
      (node (ref "J3") (pin "3") (pinfunction "3_3") (pintype "passive"))
    )
    (net (code "23") (name "DO_PK2") (class "Default")
      (node (ref "IC17") (pin "4") (pinfunction "P$4_4") (pintype "bidirectional"))
      (node (ref "J4") (pin "3") (pinfunction "3_3") (pintype "passive"))
    )
    (net (code "24") (name "FT_CTS") (class "Default")
      (node (ref "IC4") (pin "11") (pinfunction "~{CTS}_11") (pintype "input"))
      (node (ref "IC7") (pin "75") (pinfunction "PK0(A0/A8/A16)_75") (pintype "bidirectional"))
    )
    (net (code "25") (name "FT_RTS") (class "Default")
      (node (ref "IC4") (pin "3") (pinfunction "~{RTS}_3") (pintype "output"))
      (node (ref "IC7") (pin "71") (pinfunction "PJ6(A10/D6/A6/A14)_71") (pintype "bidirectional"))
    )
    (net (code "26") (name "FT_RXD") (class "Default")
      (node (ref "IC4") (pin "5") (pinfunction "RXD_5") (pintype "input"))
      (node (ref "IC7") (pin "48") (pinfunction "PF3(OC0D/TXD0)_48") (pintype "bidirectional"))
    )
    (net (code "27") (name "FT_TXD") (class "Default")
      (node (ref "IC4") (pin "1") (pinfunction "TXD_1") (pintype "output"))
      (node (ref "IC7") (pin "47") (pinfunction "PF2(OC0C/RXD0)_47") (pintype "bidirectional"))
    )
    (net (code "28") (name "GND") (class "Default")
      (node (ref "C1") (pin "2") (pinfunction "2_2") (pintype "passive"))
      (node (ref "C10") (pin "2") (pinfunction "2_2") (pintype "passive"))
      (node (ref "C11") (pin "2") (pinfunction "2_2") (pintype "passive"))
      (node (ref "C12") (pin "-") (pinfunction "-_-") (pintype "passive"))
      (node (ref "C13") (pin "2") (pinfunction "2_2") (pintype "passive"))
      (node (ref "C14") (pin "2") (pinfunction "2_2") (pintype "passive"))
      (node (ref "C15") (pin "2") (pinfunction "2_2") (pintype "passive"))
      (node (ref "C16") (pin "2") (pinfunction "2_2") (pintype "passive"))
      (node (ref "C18") (pin "2") (pinfunction "2_2") (pintype "passive"))
      (node (ref "C19") (pin "2") (pinfunction "2_2") (pintype "passive"))
      (node (ref "C2") (pin "-") (pinfunction "-_-") (pintype "passive"))
      (node (ref "C20") (pin "2") (pinfunction "2_2") (pintype "passive"))
      (node (ref "C21") (pin "2") (pinfunction "2_2") (pintype "passive"))
      (node (ref "C22") (pin "2") (pinfunction "2_2") (pintype "passive"))
      (node (ref "C23") (pin "2") (pinfunction "2_2") (pintype "passive"))
      (node (ref "C24") (pin "2") (pinfunction "2_2") (pintype "passive"))
      (node (ref "C25") (pin "2") (pinfunction "2_2") (pintype "passive"))
      (node (ref "C26") (pin "2") (pinfunction "2_2") (pintype "passive"))
      (node (ref "C27") (pin "2") (pinfunction "2_2") (pintype "passive"))
      (node (ref "C28") (pin "2") (pinfunction "2_2") (pintype "passive"))
      (node (ref "C29") (pin "2") (pinfunction "2_2") (pintype "passive"))
      (node (ref "C3") (pin "-") (pinfunction "-_-") (pintype "passive"))
      (node (ref "C30") (pin "2") (pinfunction "2_2") (pintype "passive"))
      (node (ref "C31") (pin "2") (pinfunction "2_2") (pintype "passive"))
      (node (ref "C32") (pin "2") (pinfunction "2_2") (pintype "passive"))
      (node (ref "C33") (pin "2") (pinfunction "2_2") (pintype "passive"))
      (node (ref "C34") (pin "2") (pinfunction "2_2") (pintype "passive"))
      (node (ref "C35") (pin "2") (pinfunction "2_2") (pintype "passive"))
      (node (ref "C36") (pin "2") (pinfunction "2_2") (pintype "passive"))
      (node (ref "C37") (pin "2") (pinfunction "2_2") (pintype "passive"))
      (node (ref "C38") (pin "2") (pinfunction "2_2") (pintype "passive"))
      (node (ref "C39") (pin "2") (pinfunction "2_2") (pintype "passive"))
      (node (ref "C4") (pin "2") (pinfunction "2_2") (pintype "passive"))
      (node (ref "C40") (pin "2") (pinfunction "2_2") (pintype "passive"))
      (node (ref "C41") (pin "1") (pinfunction "1_1") (pintype "passive"))
      (node (ref "C42") (pin "1") (pinfunction "1_1") (pintype "passive"))
      (node (ref "C43") (pin "2") (pinfunction "2_2") (pintype "passive"))
      (node (ref "C44") (pin "2") (pinfunction "2_2") (pintype "passive"))
      (node (ref "C45") (pin "2") (pinfunction "2_2") (pintype "passive"))
      (node (ref "C46") (pin "2") (pinfunction "2_2") (pintype "passive"))
      (node (ref "C47") (pin "2") (pinfunction "2_2") (pintype "passive"))
      (node (ref "C48") (pin "2") (pinfunction "2_2") (pintype "passive"))
      (node (ref "C49") (pin "2") (pinfunction "2_2") (pintype "passive"))
      (node (ref "C5") (pin "2") (pinfunction "2_2") (pintype "passive"))
      (node (ref "C6") (pin "2") (pinfunction "2_2") (pintype "passive"))
      (node (ref "C7") (pin "2") (pinfunction "2_2") (pintype "passive"))
      (node (ref "C8") (pin "2") (pinfunction "2_2") (pintype "passive"))
      (node (ref "C9") (pin "2") (pinfunction "2_2") (pintype "passive"))
      (node (ref "CLKIN") (pin "5") (pinfunction "5_5") (pintype "passive"))
      (node (ref "CUSB") (pin "2") (pinfunction "2_2") (pintype "passive"))
      (node (ref "IC1") (pin "P$2") (pinfunction "GND_P$2") (pintype "bidirectional"))
      (node (ref "IC10") (pin "2") (pinfunction "V-_2") (pintype "power_in"))
      (node (ref "IC11") (pin "4") (pinfunction "-VS_4") (pintype "input"))
      (node (ref "IC12") (pin "1") (pinfunction "P$1_1") (pintype "bidirectional"))
      (node (ref "IC12") (pin "3") (pinfunction "P$3_3") (pintype "bidirectional"))
      (node (ref "IC13") (pin "1") (pinfunction "P$1_1") (pintype "bidirectional"))
      (node (ref "IC13") (pin "3") (pinfunction "P$3_3") (pintype "bidirectional"))
      (node (ref "IC14") (pin "1") (pinfunction "P$1_1") (pintype "bidirectional"))
      (node (ref "IC14") (pin "3") (pinfunction "P$3_3") (pintype "bidirectional"))
      (node (ref "IC15") (pin "1") (pinfunction "P$1_1") (pintype "bidirectional"))
      (node (ref "IC15") (pin "3") (pinfunction "P$3_3") (pintype "bidirectional"))
      (node (ref "IC16") (pin "1") (pinfunction "P$1_1") (pintype "bidirectional"))
      (node (ref "IC16") (pin "3") (pinfunction "P$3_3") (pintype "bidirectional"))
      (node (ref "IC17") (pin "1") (pinfunction "P$1_1") (pintype "bidirectional"))
      (node (ref "IC17") (pin "3") (pinfunction "P$3_3") (pintype "bidirectional"))
      (node (ref "IC2") (pin "P3") (pinfunction "GND_P3") (pintype "passive"))
      (node (ref "IC3") (pin "2") (pinfunction "GND_2") (pintype "bidirectional"))
      (node (ref "IC4") (pin "18") (pinfunction "GND_18") (pintype "power_in"))
      (node (ref "IC4") (pin "21") (pinfunction "GND_21") (pintype "power_in"))
      (node (ref "IC4") (pin "25") (pinfunction "GND_25") (pintype "power_in"))
      (node (ref "IC4") (pin "26") (pinfunction "TEST_26") (pintype "input"))
      (node (ref "IC4") (pin "7") (pinfunction "GND_7") (pintype "power_in"))
      (node (ref "IC5") (pin "P$3") (pinfunction "GND_P$3") (pintype "bidirectional"))
      (node (ref "IC5") (pin "P$6") (pinfunction "GND_T_P$6") (pintype "bidirectional"))
      (node (ref "IC6") (pin "1") (pinfunction "P$1_1") (pintype "bidirectional"))
      (node (ref "IC6") (pin "3") (pinfunction "P$3_3") (pintype "bidirectional"))
      (node (ref "IC7") (pin "13") (pinfunction "GND_13") (pintype "power_in"))
      (node (ref "IC7") (pin "23") (pinfunction "GND_23") (pintype "power_in"))
      (node (ref "IC7") (pin "3") (pinfunction "GND_3") (pintype "power_in"))
      (node (ref "IC7") (pin "33") (pinfunction "GND_33") (pintype "power_in"))
      (node (ref "IC7") (pin "43") (pinfunction "GND_43") (pintype "power_in"))
      (node (ref "IC7") (pin "53") (pinfunction "GND_53") (pintype "power_in"))
      (node (ref "IC7") (pin "63") (pinfunction "GND_63") (pintype "power_in"))
      (node (ref "IC7") (pin "73") (pinfunction "GND_73") (pintype "power_in"))
      (node (ref "IC7") (pin "84") (pinfunction "GND_84") (pintype "power_in"))
      (node (ref "IC7") (pin "93") (pinfunction "GND_93") (pintype "power_in"))
      (node (ref "IC7") (pin "96") (pinfunction "PA1(ADCA1)_96") (pintype "bidirectional"))
      (node (ref "IC8") (pin "4") (pinfunction "-VS_4") (pintype "input"))
      (node (ref "IC9") (pin "2") (pinfunction "GND_2") (pintype "bidirectional"))
      (node (ref "J1") (pin "3") (pinfunction "S_3") (pintype "passive"))
      (node (ref "J2") (pin "5") (pinfunction "5_5") (pintype "passive"))
      (node (ref "J3") (pin "5") (pinfunction "5_5") (pintype "passive"))
      (node (ref "J4") (pin "5") (pinfunction "5_5") (pintype "passive"))
      (node (ref "JACK") (pin "P2") (pinfunction "2_P2") (pintype "passive"))
      (node (ref "JACK") (pin "P3") (pinfunction "3_P3") (pintype "passive"))
      (node (ref "OSC1") (pin "P$2") (pinfunction "GND_P$2") (pintype "passive"))
      (node (ref "PDI") (pin "6") (pinfunction "6_6") (pintype "passive"))
      (node (ref "Q1") (pin "2") (pinfunction "S_2") (pintype "passive"))
      (node (ref "Q10") (pin "E") (pinfunction "E_E") (pintype "passive"))
      (node (ref "Q16") (pin "3") (pinfunction "S_3") (pintype "passive"))
      (node (ref "Q17") (pin "3") (pinfunction "S_3") (pintype "passive"))
      (node (ref "Q18") (pin "3") (pinfunction "S_3") (pintype "passive"))
      (node (ref "Q3") (pin "2") (pinfunction "S_2") (pintype "passive"))
      (node (ref "Q5") (pin "E") (pinfunction "E_E") (pintype "passive"))
      (node (ref "Q6") (pin "E") (pinfunction "E_E") (pintype "passive"))
      (node (ref "Q9") (pin "E") (pinfunction "E_E") (pintype "passive"))
      (node (ref "R14") (pin "1") (pinfunction "1_1") (pintype "passive"))
      (node (ref "R25") (pin "1") (pinfunction "1_1") (pintype "passive"))
      (node (ref "R26") (pin "1") (pinfunction "1_1") (pintype "passive"))
      (node (ref "R31") (pin "1") (pinfunction "1_1") (pintype "passive"))
      (node (ref "R32") (pin "1") (pinfunction "1_1") (pintype "passive"))
      (node (ref "R39") (pin "2") (pinfunction "2_2") (pintype "passive"))
      (node (ref "R40") (pin "1") (pinfunction "1_1") (pintype "passive"))
      (node (ref "R41") (pin "2") (pinfunction "2_2") (pintype "passive"))
      (node (ref "R42") (pin "1") (pinfunction "1_1") (pintype "passive"))
      (node (ref "R43") (pin "2") (pinfunction "2_2") (pintype "passive"))
      (node (ref "R44") (pin "2") (pinfunction "2_2") (pintype "passive"))
      (node (ref "R6") (pin "1") (pinfunction "1_1") (pintype "passive"))
      (node (ref "RI2") (pin "1") (pinfunction "1_1") (pintype "passive"))
      (node (ref "RI4") (pin "1") (pinfunction "1_1") (pintype "passive"))
      (node (ref "RTRIM") (pin "1") (pinfunction "1_1") (pintype "passive"))
      (node (ref "RUSB") (pin "2") (pinfunction "2_2") (pintype "passive"))
      (node (ref "STATE") (pin "K") (pinfunction "K_K") (pintype "bidirectional"))
      (node (ref "USB") (pin "P$5") (pinfunction "5_P$5") (pintype "bidirectional"))
      (node (ref "X3") (pin "P2") (pinfunction "2_P2") (pintype "passive"))
      (node (ref "X3") (pin "P4") (pinfunction "4_P4") (pintype "passive"))
      (node (ref "X4") (pin "P3") (pinfunction "3_P3") (pintype "passive"))
      (node (ref "X5") (pin "P3") (pinfunction "3_P3") (pintype "passive"))
    )
    (net (code "29") (name "I_OFF_DAC0") (class "Default")
      (node (ref "IC7") (pin "11") (pinfunction "PB6(ADCB6/TCK)_11") (pintype "bidirectional"))
      (node (ref "R17") (pin "2") (pinfunction "2_2") (pintype "passive"))
      (node (ref "R20") (pin "1") (pinfunction "1_1") (pintype "passive"))
    )
    (net (code "30") (name "I_OFF_DAC1") (class "Default")
      (node (ref "IC7") (pin "10") (pinfunction "PB5(ADCB5/TDI)_10") (pintype "bidirectional"))
      (node (ref "R10") (pin "2") (pinfunction "2_2") (pintype "passive"))
      (node (ref "R11") (pin "1") (pinfunction "1_1") (pintype "passive"))
    )
    (net (code "31") (name "LED_5V_0") (class "Default")
      (node (ref "C35") (pin "1") (pinfunction "1_1") (pintype "passive"))
      (node (ref "IC8") (pin "7") (pinfunction "+VS_7") (pintype "input"))
      (node (ref "L3") (pin "2") (pinfunction "2_2") (pintype "passive"))
      (node (ref "X1") (pin "P1") (pinfunction "1_P1") (pintype "passive"))
    )
    (net (code "32") (name "LED_5V_1") (class "Default")
      (node (ref "C40") (pin "1") (pinfunction "1_1") (pintype "passive"))
      (node (ref "IC11") (pin "7") (pinfunction "+VS_7") (pintype "input"))
      (node (ref "L4") (pin "2") (pinfunction "2_2") (pintype "passive"))
      (node (ref "X2") (pin "P1") (pinfunction "1_P1") (pintype "passive"))
    )
    (net (code "33") (name "LED_DATA") (class "Default")
      (node (ref "IC6") (pin "2") (pinfunction "P$2_2") (pintype "bidirectional"))
      (node (ref "IC7") (pin "20") (pinfunction "PC5(OC1B/MOSI/XCK1)_20") (pintype "bidirectional"))
    )
    (net (code "34") (name "LED_RTN0") (class "Default")
      (node (ref "Q2") (pin "2") (pinfunction "D_2") (pintype "passive"))
      (node (ref "Q2") (pin "4") (pinfunction "D_4") (pintype "passive"))
      (node (ref "X1") (pin "P2") (pinfunction "2_P2") (pintype "passive"))
    )
    (net (code "35") (name "LED_RTN1") (class "Default")
      (node (ref "Q4") (pin "2") (pinfunction "D_2") (pintype "passive"))
      (node (ref "Q4") (pin "4") (pinfunction "D_4") (pintype "passive"))
      (node (ref "X2") (pin "P2") (pinfunction "2_P2") (pintype "passive"))
    )
    (net (code "36") (name "Net-(C3-Pad+)") (class "Default")
      (node (ref "C3") (pin "+") (pinfunction "+_+") (pintype "passive"))
      (node (ref "R1") (pin "1") (pinfunction "1_1") (pintype "passive"))
    )
    (net (code "37") (name "Net-(C41-Pad2)") (class "Default")
      (node (ref "C41") (pin "2") (pinfunction "2_2") (pintype "passive"))
      (node (ref "R16") (pin "2") (pinfunction "2_2") (pintype "passive"))
      (node (ref "R18") (pin "1") (pinfunction "1_1") (pintype "passive"))
    )
    (net (code "38") (name "Net-(CTUNE-Pad1)") (class "Default")
      (node (ref "CTUNE") (pin "1") (pinfunction "1_1") (pintype "passive"))
      (node (ref "RTUNE") (pin "1") (pinfunction "1_1") (pintype "passive"))
    )
    (net (code "39") (name "Net-(IC1-VBUS)") (class "Default")
      (node (ref "C5") (pin "1") (pinfunction "1_1") (pintype "passive"))
      (node (ref "IC1") (pin "P$5") (pinfunction "VBUS_P$5") (pintype "bidirectional"))
      (node (ref "L2") (pin "2") (pinfunction "2_2") (pintype "passive"))
      (node (ref "USB") (pin "P$1") (pinfunction "1_P$1") (pintype "bidirectional"))
    )
    (net (code "40") (name "Net-(IC2-ON{slash}OFF)") (class "Default")
      (node (ref "IC2") (pin "P1") (pinfunction "ON/OFF_P1") (pintype "passive"))
      (node (ref "R2") (pin "1") (pinfunction "1_1") (pintype "passive"))
    )
    (net (code "41") (name "Net-(IC2-TRIM)") (class "Default")
      (node (ref "CTUNE") (pin "2") (pinfunction "2_2") (pintype "passive"))
      (node (ref "IC2") (pin "P5") (pinfunction "TRIM_P5") (pintype "passive"))
      (node (ref "RTRIM") (pin "2") (pinfunction "2_2") (pintype "passive"))
    )
    (net (code "42") (name "Net-(IC2-VIN)") (class "Default")
      (node (ref "C4") (pin "1") (pinfunction "1_1") (pintype "passive"))
      (node (ref "IC2") (pin "P2") (pinfunction "VIN_P2") (pintype "passive"))
      (node (ref "L1") (pin "2") (pinfunction "2_2") (pintype "passive"))
      (node (ref "R1") (pin "2") (pinfunction "2_2") (pintype "passive"))
      (node (ref "R2") (pin "2") (pinfunction "2_2") (pintype "passive"))
    )
    (net (code "43") (name "Net-(IC4-3V3OUT)") (class "Default")
      (node (ref "C13") (pin "1") (pinfunction "1_1") (pintype "passive"))
      (node (ref "IC4") (pin "17") (pinfunction "3V3OUT_17") (pintype "output"))
    )
    (net (code "44") (name "Net-(IC4-CBUS0)") (class "Default")
      (node (ref "IC4") (pin "23") (pinfunction "CBUS0_23") (pintype "bidirectional"))
      (node (ref "TX") (pin "K") (pinfunction "K_K") (pintype "bidirectional"))
    )
    (net (code "45") (name "Net-(IC4-CBUS1)") (class "Default")
      (node (ref "IC4") (pin "22") (pinfunction "CBUS1_22") (pintype "bidirectional"))
      (node (ref "RX") (pin "K") (pinfunction "K_K") (pintype "bidirectional"))
    )
    (net (code "46") (name "Net-(IC5-NR{slash}FB)") (class "Default")
      (node (ref "C17") (pin "2") (pinfunction "2_2") (pintype "passive"))
      (node (ref "IC5") (pin "P$5") (pinfunction "NR/FB_P$5") (pintype "bidirectional"))
      (node (ref "R5") (pin "1") (pinfunction "1_1") (pintype "passive"))
      (node (ref "R6") (pin "2") (pinfunction "2_2") (pintype "passive"))
    )
    (net (code "47") (name "Net-(IC6-P$4)") (class "Default")
      (node (ref "IC6") (pin "4") (pinfunction "P$4_4") (pintype "bidirectional"))
      (node (ref "R7") (pin "2") (pinfunction "2_2") (pintype "passive"))
    )
    (net (code "48") (name "Net-(IC7-PR1(XTAL1))") (class "Default")
      (node (ref "IC7") (pin "92") (pinfunction "PR1(XTAL1)_92") (pintype "bidirectional"))
      (node (ref "OSC1") (pin "P$3") (pinfunction "OUTPUT_P$3") (pintype "passive"))
    )
    (net (code "49") (name "Net-(IC8-IN+)") (class "Default")
      (node (ref "C34") (pin "1") (pinfunction "1_1") (pintype "passive"))
      (node (ref "IC8") (pin "3") (pinfunction "IN+_3") (pintype "input"))
      (node (ref "R9") (pin "2") (pinfunction "2_2") (pintype "passive"))
    )
    (net (code "50") (name "Net-(IC8-OUT)") (class "Default")
      (node (ref "IC8") (pin "6") (pinfunction "OUT_6") (pintype "output"))
      (node (ref "R12") (pin "1") (pinfunction "1_1") (pintype "passive"))
    )
    (net (code "51") (name "Net-(IC10-+IN)") (class "Default")
      (node (ref "IC10") (pin "3") (pinfunction "+IN_3") (pintype "input"))
      (node (ref "R13") (pin "1") (pinfunction "1_1") (pintype "passive"))
      (node (ref "R14") (pin "2") (pinfunction "2_2") (pintype "passive"))
    )
    (net (code "52") (name "Net-(IC10--IN)") (class "Default")
      (node (ref "IC10") (pin "1") (pinfunction "OUT_1") (pintype "output"))
      (node (ref "IC10") (pin "4") (pinfunction "-IN_4") (pintype "input"))
      (node (ref "R16") (pin "1") (pinfunction "1_1") (pintype "passive"))
    )
    (net (code "53") (name "Net-(IC11-IN+)") (class "Default")
      (node (ref "C38") (pin "1") (pinfunction "1_1") (pintype "passive"))
      (node (ref "IC11") (pin "3") (pinfunction "IN+_3") (pintype "input"))
      (node (ref "R15") (pin "2") (pinfunction "2_2") (pintype "passive"))
    )
    (net (code "54") (name "Net-(IC11-OUT)") (class "Default")
      (node (ref "IC11") (pin "6") (pinfunction "OUT_6") (pintype "output"))
      (node (ref "R19") (pin "1") (pinfunction "1_1") (pintype "passive"))
    )
    (net (code "55") (name "Net-(JACK-1)") (class "Default")
      (node (ref "F1") (pin "2") (pinfunction "2_2") (pintype "passive"))
      (node (ref "JACK") (pin "P1") (pinfunction "1_P1") (pintype "passive"))
    )
    (net (code "56") (name "Net-(Q1-D)") (class "Default")
      (node (ref "Q1") (pin "3") (pinfunction "D_3") (pintype "passive"))
      (node (ref "Q2") (pin "1") (pinfunction "G_1") (pintype "passive"))
      (node (ref "R12") (pin "2") (pinfunction "2_2") (pintype "passive"))
    )
    (net (code "57") (name "Net-(Q1-G)") (class "Default")
      (node (ref "C37") (pin "1") (pinfunction "1_1") (pintype "passive"))
      (node (ref "Q1") (pin "1") (pinfunction "G_1") (pintype "passive"))
      (node (ref "R11") (pin "2") (pinfunction "2_2") (pintype "passive"))
    )
    (net (code "58") (name "Net-(Q3-D)") (class "Default")
      (node (ref "Q3") (pin "3") (pinfunction "D_3") (pintype "passive"))
      (node (ref "Q4") (pin "1") (pinfunction "G_1") (pintype "passive"))
      (node (ref "R19") (pin "2") (pinfunction "2_2") (pintype "passive"))
    )
    (net (code "59") (name "Net-(Q3-G)") (class "Default")
      (node (ref "C43") (pin "1") (pinfunction "1_1") (pintype "passive"))
      (node (ref "Q3") (pin "1") (pinfunction "G_1") (pintype "passive"))
      (node (ref "R20") (pin "2") (pinfunction "2_2") (pintype "passive"))
    )
    (net (code "60") (name "Net-(Q5-PadB)") (class "Default")
      (node (ref "Q5") (pin "B") (pinfunction "B_B") (pintype "passive"))
      (node (ref "R21") (pin "2") (pinfunction "2_2") (pintype "passive"))
    )
    (net (code "61") (name "Net-(Q6-PadB)") (class "Default")
      (node (ref "Q6") (pin "B") (pinfunction "B_B") (pintype "passive"))
      (node (ref "R22") (pin "2") (pinfunction "2_2") (pintype "passive"))
    )
    (net (code "62") (name "Net-(Q7-G)") (class "Default")
      (node (ref "Q5") (pin "C") (pinfunction "C_C") (pintype "passive"))
      (node (ref "Q7") (pin "1") (pinfunction "G_1") (pintype "passive"))
      (node (ref "R23") (pin "2") (pinfunction "2_2") (pintype "passive"))
    )
    (net (code "63") (name "Net-(Q8-G)") (class "Default")
      (node (ref "Q6") (pin "C") (pinfunction "C_C") (pintype "passive"))
      (node (ref "Q8") (pin "1") (pinfunction "G_1") (pintype "passive"))
      (node (ref "R24") (pin "2") (pinfunction "2_2") (pintype "passive"))
    )
    (net (code "64") (name "Net-(Q9-PadB)") (class "Default")
      (node (ref "Q9") (pin "B") (pinfunction "B_B") (pintype "passive"))
      (node (ref "R27") (pin "2") (pinfunction "2_2") (pintype "passive"))
    )
    (net (code "65") (name "Net-(Q10-PadB)") (class "Default")
      (node (ref "Q10") (pin "B") (pinfunction "B_B") (pintype "passive"))
      (node (ref "R28") (pin "2") (pinfunction "2_2") (pintype "passive"))
    )
    (net (code "66") (name "Net-(Q11-G)") (class "Default")
      (node (ref "Q11") (pin "1") (pinfunction "G_1") (pintype "passive"))
      (node (ref "Q9") (pin "C") (pinfunction "C_C") (pintype "passive"))
      (node (ref "R29") (pin "2") (pinfunction "2_2") (pintype "passive"))
    )
    (net (code "67") (name "Net-(Q12-G)") (class "Default")
      (node (ref "Q10") (pin "C") (pinfunction "C_C") (pintype "passive"))
      (node (ref "Q12") (pin "1") (pinfunction "G_1") (pintype "passive"))
      (node (ref "R30") (pin "2") (pinfunction "2_2") (pintype "passive"))
    )
    (net (code "68") (name "Net-(Q16-G)") (class "Default")
      (node (ref "Q16") (pin "1") (pinfunction "G_1") (pintype "passive"))
      (node (ref "R45") (pin "2") (pinfunction "2_2") (pintype "passive"))
    )
    (net (code "69") (name "Net-(Q17-G)") (class "Default")
      (node (ref "Q17") (pin "1") (pinfunction "G_1") (pintype "passive"))
      (node (ref "R46") (pin "2") (pinfunction "2_2") (pintype "passive"))
    )
    (net (code "70") (name "Net-(Q18-G)") (class "Default")
      (node (ref "Q18") (pin "1") (pinfunction "G_1") (pintype "passive"))
      (node (ref "R47") (pin "2") (pinfunction "2_2") (pintype "passive"))
    )
    (net (code "71") (name "Net-(R3-Pad1)") (class "Default")
      (node (ref "R3") (pin "1") (pinfunction "1_1") (pintype "passive"))
      (node (ref "TX") (pin "A") (pinfunction "A_A") (pintype "bidirectional"))
    )
    (net (code "72") (name "Net-(R4-Pad1)") (class "Default")
      (node (ref "R4") (pin "1") (pinfunction "1_1") (pintype "passive"))
      (node (ref "RX") (pin "A") (pinfunction "A_A") (pintype "bidirectional"))
    )
    (net (code "73") (name "Net-(R8-Pad1)") (class "Default")
      (node (ref "R8") (pin "1") (pinfunction "1_1") (pintype "passive"))
      (node (ref "STATE") (pin "A") (pinfunction "A_A") (pintype "bidirectional"))
    )
    (net (code "74") (name "Net-(RI1-Pad1)") (class "Default")
      (node (ref "RI1") (pin "1") (pinfunction "1_1") (pintype "passive"))
      (node (ref "RI2") (pin "2") (pinfunction "2_2") (pintype "passive"))
    )
    (net (code "75") (name "Net-(RI3-Pad1)") (class "Default")
      (node (ref "RI3") (pin "1") (pinfunction "1_1") (pintype "passive"))
      (node (ref "RI4") (pin "2") (pinfunction "2_2") (pintype "passive"))
    )
    (net (code "76") (name "Net-(USB-2)") (class "Default")
      (node (ref "IC1") (pin "P$1") (pinfunction "IO1_P$1") (pintype "bidirectional"))
      (node (ref "USB") (pin "P$2") (pinfunction "2_P$2") (pintype "bidirectional"))
    )
    (net (code "77") (name "Net-(USB-3)") (class "Default")
      (node (ref "IC1") (pin "P$3") (pinfunction "IO2_P$3") (pintype "bidirectional"))
      (node (ref "USB") (pin "P$3") (pinfunction "3_P$3") (pintype "bidirectional"))
    )
    (net (code "78") (name "Net-(USB-P$1)") (class "Default")
      (node (ref "RUSB") (pin "1") (pinfunction "1_1") (pintype "passive"))
      (node (ref "USB") (pin "SHIELD_1") (pinfunction "P$1_SHIELD_1") (pintype "bidirectional"))
    )
    (net (code "79") (name "Net-(USB-P$4)") (class "Default")
      (node (ref "CUSB") (pin "1") (pinfunction "1_1") (pintype "passive"))
      (node (ref "USB") (pin "SHIELD_4") (pinfunction "P$4_SHIELD_4") (pintype "bidirectional"))
    )
    (net (code "80") (name "P5.45V") (class "Default")
      (node (ref "C14") (pin "1") (pinfunction "1_1") (pintype "passive"))
      (node (ref "C8") (pin "1") (pinfunction "1_1") (pintype "passive"))
      (node (ref "C9") (pin "1") (pinfunction "1_1") (pintype "passive"))
      (node (ref "IC2") (pin "P4") (pinfunction "VOUT_P4") (pintype "passive"))
      (node (ref "IC5") (pin "P$1") (pinfunction "EN_P$1") (pintype "bidirectional"))
      (node (ref "IC5") (pin "P$2") (pinfunction "IN_P$2") (pintype "bidirectional"))
      (node (ref "RTUNE") (pin "2") (pinfunction "2_2") (pintype "passive"))
    )
    (net (code "81") (name "PDI-CLK") (class "Default")
      (node (ref "IC7") (pin "90") (pinfunction "PDI-CLK/~{RESET}_90") (pintype "input"))
      (node (ref "PDI") (pin "5") (pinfunction "5_5") (pintype "passive"))
    )
    (net (code "82") (name "PDI-DATA") (class "Default")
      (node (ref "IC7") (pin "89") (pinfunction "PDI-DATA_89") (pintype "bidirectional"))
      (node (ref "PDI") (pin "1") (pinfunction "1_1") (pintype "passive"))
    )
    (net (code "83") (name "PK0_IN") (class "Default")
      (node (ref "IC12") (pin "4") (pinfunction "P$4_4") (pintype "bidirectional"))
      (node (ref "IC7") (pin "29") (pinfunction "PD4(OC1A/~{SS})_29") (pintype "bidirectional"))
    )
    (net (code "84") (name "PK0_IO") (class "Default")
      (node (ref "IC7") (pin "30") (pinfunction "PD5(OC1B/XCK1/MOSI)_30") (pintype "bidirectional"))
      (node (ref "Q15") (pin "2") (pinfunction "S_2") (pintype "passive"))
      (node (ref "R35") (pin "2") (pinfunction "2_2") (pintype "passive"))
    )
    (net (code "85") (name "PK0_OUT") (class "Default")
      (node (ref "IC13") (pin "2") (pinfunction "P$2_2") (pintype "bidirectional"))
      (node (ref "IC7") (pin "31") (pinfunction "PD6(RXD1/MISO)_31") (pintype "bidirectional"))
      (node (ref "R40") (pin "2") (pinfunction "2_2") (pintype "passive"))
    )
    (net (code "86") (name "PK0_VAL") (class "Default")
      (node (ref "IC7") (pin "32") (pinfunction "PD7(TXD1/SCK/CLKO/EVO)_32") (pintype "bidirectional"))
      (node (ref "R45") (pin "1") (pinfunction "1_1") (pintype "passive"))
    )
    (net (code "87") (name "PK1_IN") (class "Default")
      (node (ref "IC14") (pin "4") (pinfunction "P$4_4") (pintype "bidirectional"))
      (node (ref "IC7") (pin "39") (pinfunction "PE4(OC1A/~{SS})_39") (pintype "bidirectional"))
    )
    (net (code "88") (name "PK1_IO") (class "Default")
      (node (ref "IC7") (pin "40") (pinfunction "PE5(OC1B/XCK1/MOSI)_40") (pintype "bidirectional"))
      (node (ref "Q13") (pin "2") (pinfunction "S_2") (pintype "passive"))
      (node (ref "R33") (pin "2") (pinfunction "2_2") (pintype "passive"))
    )
    (net (code "89") (name "PK1_OUT") (class "Default")
      (node (ref "IC15") (pin "2") (pinfunction "P$2_2") (pintype "bidirectional"))
      (node (ref "IC7") (pin "41") (pinfunction "PE6(RSC1/MISO/TOSC2)_41") (pintype "bidirectional"))
      (node (ref "R42") (pin "2") (pinfunction "2_2") (pintype "passive"))
    )
    (net (code "90") (name "PK1_VAL") (class "Default")
      (node (ref "IC7") (pin "42") (pinfunction "PE7(TSD1/SCK/CLKO/EVO/TOSC1)_42") (pintype "bidirectional"))
      (node (ref "R46") (pin "1") (pinfunction "1_1") (pintype "passive"))
    )
    (net (code "91") (name "PK2_IN") (class "Default")
      (node (ref "IC16") (pin "4") (pinfunction "P$4_4") (pintype "bidirectional"))
      (node (ref "IC7") (pin "49") (pinfunction "PF4(OC1A/~{SS})_49") (pintype "bidirectional"))
    )
    (net (code "92") (name "PK2_IO") (class "Default")
      (node (ref "IC7") (pin "50") (pinfunction "PF5(OC1B/XCK1/MOSI)_50") (pintype "bidirectional"))
      (node (ref "Q14") (pin "2") (pinfunction "S_2") (pintype "passive"))
      (node (ref "R34") (pin "2") (pinfunction "2_2") (pintype "passive"))
    )
    (net (code "93") (name "PK2_OUT") (class "Default")
      (node (ref "IC17") (pin "2") (pinfunction "P$2_2") (pintype "bidirectional"))
      (node (ref "IC7") (pin "51") (pinfunction "PF6(RXD1/MISO)_51") (pintype "bidirectional"))
      (node (ref "R44") (pin "1") (pinfunction "1_1") (pintype "passive"))
    )
    (net (code "94") (name "PK2_VAL") (class "Default")
      (node (ref "IC7") (pin "52") (pinfunction "PF7(TXD1/SCK)_52") (pintype "bidirectional"))
      (node (ref "R47") (pin "1") (pinfunction "1_1") (pintype "passive"))
    )
    (net (code "95") (name "SERIAL_LED0") (class "Default")
      (node (ref "J1") (pin "2") (pinfunction "S_2") (pintype "passive"))
      (node (ref "R7") (pin "1") (pinfunction "1_1") (pintype "passive"))
    )
    (net (code "96") (name "STATE") (class "Default")
      (node (ref "IC7") (pin "1") (pinfunction "PA6(ADCA6)_1") (pintype "bidirectional"))
      (node (ref "R8") (pin "2") (pinfunction "2_2") (pintype "passive"))
    )
    (net (code "97") (name "TOG_D00") (class "Default")
      (node (ref "IC7") (pin "45") (pinfunction "PF0(OC0A/SDA)_45") (pintype "bidirectional"))
      (node (ref "R28") (pin "1") (pinfunction "1_1") (pintype "passive"))
    )
    (net (code "98") (name "TOG_D01") (class "Default")
      (node (ref "IC7") (pin "35") (pinfunction "PE0(OC0A/SDA)_35") (pintype "bidirectional"))
      (node (ref "R22") (pin "1") (pinfunction "1_1") (pintype "passive"))
    )
    (net (code "99") (name "TOG_D02") (class "Default")
      (node (ref "IC7") (pin "25") (pinfunction "PD0(OC0A/SDA)_25") (pintype "bidirectional"))
      (node (ref "R27") (pin "1") (pinfunction "1_1") (pintype "passive"))
    )
    (net (code "100") (name "TOG_D03") (class "Default")
      (node (ref "IC7") (pin "15") (pinfunction "PC0(OC0A/SDA)_15") (pintype "bidirectional"))
      (node (ref "R21") (pin "1") (pinfunction "1_1") (pintype "passive"))
    )
    (net (code "101") (name "USBDM") (class "Default")
      (node (ref "C7") (pin "1") (pinfunction "1_1") (pintype "passive"))
      (node (ref "IC1") (pin "P$6") (pinfunction "IO1_P$6") (pintype "bidirectional"))
      (node (ref "IC4") (pin "16") (pinfunction "USBDM_16") (pintype "bidirectional"))
    )
    (net (code "102") (name "USBDP") (class "Default")
      (node (ref "C6") (pin "1") (pinfunction "1_1") (pintype "passive"))
      (node (ref "IC1") (pin "P$4") (pinfunction "IO2_P$4") (pintype "bidirectional"))
      (node (ref "IC4") (pin "15") (pinfunction "USBDP_15") (pintype "bidirectional"))
    )
    (net (code "103") (name "VAL_PK0") (class "Default")
      (node (ref "D1") (pin "A") (pinfunction "A_A") (pintype "passive"))
      (node (ref "J2") (pin "7") (pinfunction "7_7") (pintype "passive"))
      (node (ref "Q16") (pin "2") (pinfunction "D_2") (pintype "passive"))
      (node (ref "Q16") (pin "4") (pinfunction "D_4") (pintype "passive"))
    )
    (net (code "104") (name "VAL_PK1") (class "Default")
      (node (ref "D2") (pin "A") (pinfunction "A_A") (pintype "passive"))
      (node (ref "J3") (pin "7") (pinfunction "7_7") (pintype "passive"))
      (node (ref "Q17") (pin "2") (pinfunction "D_2") (pintype "passive"))
      (node (ref "Q17") (pin "4") (pinfunction "D_4") (pintype "passive"))
    )
    (net (code "105") (name "VAL_PK2") (class "Default")
      (node (ref "D3") (pin "A") (pinfunction "A_A") (pintype "passive"))
      (node (ref "J4") (pin "7") (pinfunction "7_7") (pintype "passive"))
      (node (ref "Q18") (pin "2") (pinfunction "D_2") (pintype "passive"))
      (node (ref "Q18") (pin "4") (pinfunction "D_4") (pintype "passive"))
    )
    (net (code "106") (name "VCCIO") (class "Default")
      (node (ref "C15") (pin "1") (pinfunction "1_1") (pintype "passive"))
      (node (ref "C16") (pin "1") (pinfunction "1_1") (pintype "passive"))
      (node (ref "C20") (pin "1") (pinfunction "1_1") (pintype "passive"))
      (node (ref "C21") (pin "1") (pinfunction "1_1") (pintype "passive"))
      (node (ref "C22") (pin "1") (pinfunction "1_1") (pintype "passive"))
      (node (ref "C23") (pin "1") (pinfunction "1_1") (pintype "passive"))
      (node (ref "C24") (pin "1") (pinfunction "1_1") (pintype "passive"))
      (node (ref "C26") (pin "1") (pinfunction "1_1") (pintype "passive"))
      (node (ref "C28") (pin "1") (pinfunction "1_1") (pintype "passive"))
      (node (ref "C30") (pin "1") (pinfunction "1_1") (pintype "passive"))
      (node (ref "C31") (pin "1") (pinfunction "1_1") (pintype "passive"))
      (node (ref "C32") (pin "1") (pinfunction "1_1") (pintype "passive"))
      (node (ref "C44") (pin "1") (pinfunction "1_1") (pintype "passive"))
      (node (ref "C46") (pin "1") (pinfunction "1_1") (pintype "passive"))
      (node (ref "C48") (pin "1") (pinfunction "1_1") (pintype "passive"))
      (node (ref "CLKIN") (pin "1") (pinfunction "1_1") (pintype "passive"))
      (node (ref "D4") (pin "A") (pinfunction "A_A") (pintype "passive"))
      (node (ref "IC12") (pin "5") (pinfunction "P$5_5") (pintype "bidirectional"))
      (node (ref "IC14") (pin "5") (pinfunction "P$5_5") (pintype "bidirectional"))
      (node (ref "IC16") (pin "5") (pinfunction "P$5_5") (pintype "bidirectional"))
      (node (ref "IC3") (pin "5") (pinfunction "OUT_5") (pintype "bidirectional"))
      (node (ref "IC4") (pin "4") (pinfunction "VCCIO_4") (pintype "power_in"))
      (node (ref "IC7") (pin "14") (pinfunction "VCC_14") (pintype "power_in"))
      (node (ref "IC7") (pin "24") (pinfunction "VCC_24") (pintype "power_in"))
      (node (ref "IC7") (pin "34") (pinfunction "VCC_34") (pintype "power_in"))
      (node (ref "IC7") (pin "44") (pinfunction "VCC_44") (pintype "power_in"))
      (node (ref "IC7") (pin "54") (pinfunction "VCC_54") (pintype "power_in"))
      (node (ref "IC7") (pin "64") (pinfunction "VCC_64") (pintype "power_in"))
      (node (ref "IC7") (pin "74") (pinfunction "VCC_74") (pintype "power_in"))
      (node (ref "IC7") (pin "83") (pinfunction "VCC_83") (pintype "power_in"))
      (node (ref "OSC1") (pin "P$4") (pinfunction "VDD_P$4") (pintype "passive"))
      (node (ref "PDI") (pin "2") (pinfunction "2_2") (pintype "passive"))
      (node (ref "Q13") (pin "1") (pinfunction "G_1") (pintype "passive"))
      (node (ref "Q14") (pin "1") (pinfunction "G_1") (pintype "passive"))
      (node (ref "Q15") (pin "1") (pinfunction "G_1") (pintype "passive"))
      (node (ref "R10") (pin "1") (pinfunction "1_1") (pintype "passive"))
      (node (ref "R17") (pin "1") (pinfunction "1_1") (pintype "passive"))
      (node (ref "R33") (pin "1") (pinfunction "1_1") (pintype "passive"))
      (node (ref "R34") (pin "1") (pinfunction "1_1") (pintype "passive"))
      (node (ref "R35") (pin "1") (pinfunction "1_1") (pintype "passive"))
    )
    (net (code "107") (name "VDD") (class "Default")
      (node (ref "C25") (pin "1") (pinfunction "1_1") (pintype "passive"))
      (node (ref "C27") (pin "1") (pinfunction "1_1") (pintype "passive"))
      (node (ref "C29") (pin "1") (pinfunction "1_1") (pintype "passive"))
      (node (ref "C36") (pin "1") (pinfunction "1_1") (pintype "passive"))
      (node (ref "C39") (pin "1") (pinfunction "1_1") (pintype "passive"))
      (node (ref "D4") (pin "C") (pinfunction "C_C") (pintype "passive"))
      (node (ref "IC10") (pin "5") (pinfunction "V+_5") (pintype "power_in"))
      (node (ref "IC7") (pin "4") (pinfunction "AVCC-B_4") (pintype "power_in"))
      (node (ref "IC7") (pin "94") (pinfunction "AVCC-A_94") (pintype "power_in"))
      (node (ref "IC9") (pin "5") (pinfunction "OUT_5") (pintype "bidirectional"))
    )
    (net (code "108") (name "unconnected-(IC3-N{slash}C-Pad4)") (class "Default")
      (node (ref "IC3") (pin "4") (pinfunction "N/C_4") (pintype "bidirectional"))
    )
    (net (code "109") (name "unconnected-(IC4-CBUS2-Pad13)") (class "Default")
      (node (ref "IC4") (pin "13") (pinfunction "CBUS2_13") (pintype "bidirectional"))
    )
    (net (code "110") (name "unconnected-(IC4-CBUS3-Pad14)") (class "Default")
      (node (ref "IC4") (pin "14") (pinfunction "CBUS3_14") (pintype "bidirectional"))
    )
    (net (code "111") (name "unconnected-(IC4-CBUS4-Pad12)") (class "Default")
      (node (ref "IC4") (pin "12") (pinfunction "CBUS4_12") (pintype "bidirectional"))
    )
    (net (code "112") (name "unconnected-(IC4-OSCI-Pad27)") (class "Default")
      (node (ref "IC4") (pin "27") (pinfunction "OSCI_27") (pintype "input"))
    )
    (net (code "113") (name "unconnected-(IC4-OSCO-Pad28)") (class "Default")
      (node (ref "IC4") (pin "28") (pinfunction "OSCO_28") (pintype "output"))
    )
    (net (code "114") (name "unconnected-(IC4-~{DCD}-Pad10)") (class "Default")
      (node (ref "IC4") (pin "10") (pinfunction "~{DCD}_10") (pintype "input"))
    )
    (net (code "115") (name "unconnected-(IC4-~{DSR}-Pad9)") (class "Default")
      (node (ref "IC4") (pin "9") (pinfunction "~{DSR}_9") (pintype "input"))
    )
    (net (code "116") (name "unconnected-(IC4-~{DTR}-Pad2)") (class "Default")
      (node (ref "IC4") (pin "2") (pinfunction "~{DTR}_2") (pintype "output"))
    )
    (net (code "117") (name "unconnected-(IC4-~{RESET}-Pad19)") (class "Default")
      (node (ref "IC4") (pin "19") (pinfunction "~{RESET}_19") (pintype "input"))
    )
    (net (code "118") (name "unconnected-(IC4-~{RI}-Pad6)") (class "Default")
      (node (ref "IC4") (pin "6") (pinfunction "~{RI}_6") (pintype "input"))
    )
    (net (code "119") (name "unconnected-(IC7-PA2(ADCA2)-Pad97)") (class "Default")
      (node (ref "IC7") (pin "97") (pinfunction "PA2(ADCA2)_97") (pintype "bidirectional"))
    )
    (net (code "120") (name "unconnected-(IC7-PA3(ADCA3)-Pad98)") (class "Default")
      (node (ref "IC7") (pin "98") (pinfunction "PA3(ADCA3)_98") (pintype "bidirectional"))
    )
    (net (code "121") (name "unconnected-(IC7-PA4(ADCA4)-Pad99)") (class "Default")
      (node (ref "IC7") (pin "99") (pinfunction "PA4(ADCA4)_99") (pintype "bidirectional"))
    )
    (net (code "122") (name "unconnected-(IC7-PA5(ADCA5)-Pad100)") (class "Default")
      (node (ref "IC7") (pin "100") (pinfunction "PA5(ADCA5)_100") (pintype "bidirectional"))
    )
    (net (code "123") (name "unconnected-(IC7-PA7{slash}(ADCA7{slash}AC0-OUT)-Pad2)") (class "Default")
      (node (ref "IC7") (pin "2") (pinfunction "PA7/(ADCA7/AC0-OUT)_2") (pintype "bidirectional"))
    )
    (net (code "124") (name "unconnected-(IC7-PB0(ADCB0{slash}AREFB)-Pad5)") (class "Default")
      (node (ref "IC7") (pin "5") (pinfunction "PB0(ADCB0/AREFB)_5") (pintype "bidirectional"))
    )
    (net (code "125") (name "unconnected-(IC7-PB1(ADCB1)-Pad6)") (class "Default")
      (node (ref "IC7") (pin "6") (pinfunction "PB1(ADCB1)_6") (pintype "bidirectional"))
    )
    (net (code "126") (name "unconnected-(IC7-PB4(ADCB4{slash}TMS)-Pad9)") (class "Default")
      (node (ref "IC7") (pin "9") (pinfunction "PB4(ADCB4/TMS)_9") (pintype "bidirectional"))
    )
    (net (code "127") (name "unconnected-(IC7-PB7(ADCB7{slash}AC0-OUT{slash}TDO)-Pad12)") (class "Default")
      (node (ref "IC7") (pin "12") (pinfunction "PB7(ADCB7/AC0-OUT/TDO)_12") (pintype "bidirectional"))
    )
    (net (code "128") (name "unconnected-(IC7-PC1(OC0B{slash}XCK0{slash}SCL)-Pad16)") (class "Default")
      (node (ref "IC7") (pin "16") (pinfunction "PC1(OC0B/XCK0/SCL)_16") (pintype "bidirectional"))
    )
    (net (code "129") (name "unconnected-(IC7-PC2(OC0C{slash}RXD0)-Pad17)") (class "Default")
      (node (ref "IC7") (pin "17") (pinfunction "PC2(OC0C/RXD0)_17") (pintype "bidirectional"))
    )
    (net (code "130") (name "unconnected-(IC7-PC3(OC0D{slash}TXD0)-Pad18)") (class "Default")
      (node (ref "IC7") (pin "18") (pinfunction "PC3(OC0D/TXD0)_18") (pintype "bidirectional"))
    )
    (net (code "131") (name "unconnected-(IC7-PC4(OC1A{slash}~{SS})-Pad19)") (class "Default")
      (node (ref "IC7") (pin "19") (pinfunction "PC4(OC1A/~{SS})_19") (pintype "bidirectional"))
    )
    (net (code "132") (name "unconnected-(IC7-PC7(SCK{slash}TXD1{slash}CLKO{slash}EVO)-Pad22)") (class "Default")
      (node (ref "IC7") (pin "22") (pinfunction "PC7(SCK/TXD1/CLKO/EVO)_22") (pintype "bidirectional"))
    )
    (net (code "133") (name "unconnected-(IC7-PD1(OC0B{slash}XCK0{slash}SCL)-Pad26)") (class "Default")
      (node (ref "IC7") (pin "26") (pinfunction "PD1(OC0B/XCK0/SCL)_26") (pintype "bidirectional"))
    )
    (net (code "134") (name "unconnected-(IC7-PD2(OC0C{slash}RXD0)-Pad27)") (class "Default")
      (node (ref "IC7") (pin "27") (pinfunction "PD2(OC0C/RXD0)_27") (pintype "bidirectional"))
    )
    (net (code "135") (name "unconnected-(IC7-PD3(OC0D{slash}TXD0)-Pad28)") (class "Default")
      (node (ref "IC7") (pin "28") (pinfunction "PD3(OC0D/TXD0)_28") (pintype "bidirectional"))
    )
    (net (code "136") (name "unconnected-(IC7-PE1(OC0B{slash}XCK0{slash}SCL)-Pad36)") (class "Default")
      (node (ref "IC7") (pin "36") (pinfunction "PE1(OC0B/XCK0/SCL)_36") (pintype "bidirectional"))
    )
    (net (code "137") (name "unconnected-(IC7-PE2(OC0C{slash}RXD0)-Pad37)") (class "Default")
      (node (ref "IC7") (pin "37") (pinfunction "PE2(OC0C/RXD0)_37") (pintype "bidirectional"))
    )
    (net (code "138") (name "unconnected-(IC7-PE3(OC0D{slash}TXD0)-Pad38)") (class "Default")
      (node (ref "IC7") (pin "38") (pinfunction "PE3(OC0D/TXD0)_38") (pintype "bidirectional"))
    )
    (net (code "139") (name "unconnected-(IC7-PF1(OC0B{slash}XCK0{slash}SCL)-Pad46)") (class "Default")
      (node (ref "IC7") (pin "46") (pinfunction "PF1(OC0B/XCK0/SCL)_46") (pintype "bidirectional"))
    )
    (net (code "140") (name "unconnected-(IC7-PH0(~{WE})-Pad55)") (class "Default")
      (node (ref "IC7") (pin "55") (pinfunction "PH0(~{WE})_55") (pintype "bidirectional"))
    )
    (net (code "141") (name "unconnected-(IC7-PH1(~{CAS}{slash}~{RE})-Pad56)") (class "Default")
      (node (ref "IC7") (pin "56") (pinfunction "PH1(~{CAS}/~{RE})_56") (pintype "bidirectional"))
    )
    (net (code "142") (name "unconnected-(IC7-PH2(~{RAS}{slash}ALE1)-Pad57)") (class "Default")
      (node (ref "IC7") (pin "57") (pinfunction "PH2(~{RAS}/ALE1)_57") (pintype "bidirectional"))
    )
    (net (code "143") (name "unconnected-(IC7-PH3(~{DOM}{slash}ALE2)-Pad58)") (class "Default")
      (node (ref "IC7") (pin "58") (pinfunction "PH3(~{DOM}/ALE2)_58") (pintype "bidirectional"))
    )
    (net (code "144") (name "unconnected-(IC7-PH4(BA0{slash}~{CS0}{slash}A16)-Pad59)") (class "Default")
      (node (ref "IC7") (pin "59") (pinfunction "PH4(BA0/~{CS0}/A16)_59") (pintype "bidirectional"))
    )
    (net (code "145") (name "unconnected-(IC7-PH5(BA1{slash}~{CS1}{slash}A17)-Pad60)") (class "Default")
      (node (ref "IC7") (pin "60") (pinfunction "PH5(BA1/~{CS1}/A17)_60") (pintype "bidirectional"))
    )
    (net (code "146") (name "unconnected-(IC7-PH6(CKE{slash}~{CS2}{slash}A18)-Pad61)") (class "Default")
      (node (ref "IC7") (pin "61") (pinfunction "PH6(CKE/~{CS2}/A18)_61") (pintype "bidirectional"))
    )
    (net (code "147") (name "unconnected-(IC7-PH7(CLK{slash}~{CS3}{slash}A19)-Pad62)") (class "Default")
      (node (ref "IC7") (pin "62") (pinfunction "PH7(CLK/~{CS3}/A19)_62") (pintype "bidirectional"))
    )
    (net (code "148") (name "unconnected-(IC7-PJ0(D0{slash}A0{slash}A8)-Pad65)") (class "Default")
      (node (ref "IC7") (pin "65") (pinfunction "PJ0(D0/A0/A8)_65") (pintype "bidirectional"))
    )
    (net (code "149") (name "unconnected-(IC7-PJ1(D1{slash}A1{slash}A9)-Pad66)") (class "Default")
      (node (ref "IC7") (pin "66") (pinfunction "PJ1(D1/A1/A9)_66") (pintype "bidirectional"))
    )
    (net (code "150") (name "unconnected-(IC7-PJ2(D2{slash}A2{slash}A10)-Pad67)") (class "Default")
      (node (ref "IC7") (pin "67") (pinfunction "PJ2(D2/A2/A10)_67") (pintype "bidirectional"))
    )
    (net (code "151") (name "unconnected-(IC7-PJ3(D3{slash}A3{slash}A11)-Pad68)") (class "Default")
      (node (ref "IC7") (pin "68") (pinfunction "PJ3(D3/A3/A11)_68") (pintype "bidirectional"))
    )
    (net (code "152") (name "unconnected-(IC7-PJ4(A8{slash}D4{slash}A4{slash}A12)-Pad69)") (class "Default")
      (node (ref "IC7") (pin "69") (pinfunction "PJ4(A8/D4/A4/A12)_69") (pintype "bidirectional"))
    )
    (net (code "153") (name "unconnected-(IC7-PJ5(A9{slash}D5{slash}A5{slash}A13)-Pad70)") (class "Default")
      (node (ref "IC7") (pin "70") (pinfunction "PJ5(A9/D5/A5/A13)_70") (pintype "bidirectional"))
    )
    (net (code "154") (name "unconnected-(IC7-PJ7(A11{slash}D7{slash}A7{slash}A15)-Pad72)") (class "Default")
      (node (ref "IC7") (pin "72") (pinfunction "PJ7(A11/D7/A7/A15)_72") (pintype "bidirectional"))
    )
    (net (code "155") (name "unconnected-(IC7-PK1(A1{slash}A9{slash}A17)-Pad76)") (class "Default")
      (node (ref "IC7") (pin "76") (pinfunction "PK1(A1/A9/A17)_76") (pintype "bidirectional"))
    )
    (net (code "156") (name "unconnected-(IC7-PK2(A2{slash}A10{slash}A18)-Pad77)") (class "Default")
      (node (ref "IC7") (pin "77") (pinfunction "PK2(A2/A10/A18)_77") (pintype "bidirectional"))
    )
    (net (code "157") (name "unconnected-(IC7-PK3(A3{slash}A11{slash}A19)-Pad78)") (class "Default")
      (node (ref "IC7") (pin "78") (pinfunction "PK3(A3/A11/A19)_78") (pintype "bidirectional"))
    )
    (net (code "158") (name "unconnected-(IC7-PK4(A4{slash}A12{slash}A20)-Pad79)") (class "Default")
      (node (ref "IC7") (pin "79") (pinfunction "PK4(A4/A12/A20)_79") (pintype "bidirectional"))
    )
    (net (code "159") (name "unconnected-(IC7-PK5(A5{slash}A13{slash}A22)-Pad80)") (class "Default")
      (node (ref "IC7") (pin "80") (pinfunction "PK5(A5/A13/A22)_80") (pintype "bidirectional"))
    )
    (net (code "160") (name "unconnected-(IC7-PK6(A6{slash}A14{slash}A22)-Pad81)") (class "Default")
      (node (ref "IC7") (pin "81") (pinfunction "PK6(A6/A14/A22)_81") (pintype "bidirectional"))
    )
    (net (code "161") (name "unconnected-(IC7-PK7(A7{slash}A15{slash}A23)-Pad82)") (class "Default")
      (node (ref "IC7") (pin "82") (pinfunction "PK7(A7/A15/A23)_82") (pintype "bidirectional"))
    )
    (net (code "162") (name "unconnected-(IC7-PQ0(TOSC1)-Pad85)") (class "Default")
      (node (ref "IC7") (pin "85") (pinfunction "PQ0(TOSC1)_85") (pintype "bidirectional"))
    )
    (net (code "163") (name "unconnected-(IC7-PQ1(TOSC2)-Pad86)") (class "Default")
      (node (ref "IC7") (pin "86") (pinfunction "PQ1(TOSC2)_86") (pintype "bidirectional"))
    )
    (net (code "164") (name "unconnected-(IC7-PQ2-Pad87)") (class "Default")
      (node (ref "IC7") (pin "87") (pinfunction "PQ2_87") (pintype "bidirectional"))
    )
    (net (code "165") (name "unconnected-(IC7-PQ3-Pad88)") (class "Default")
      (node (ref "IC7") (pin "88") (pinfunction "PQ3_88") (pintype "bidirectional"))
    )
    (net (code "166") (name "unconnected-(IC7-PR0(XTAL2)-Pad91)") (class "Default")
      (node (ref "IC7") (pin "91") (pinfunction "PR0(XTAL2)_91") (pintype "bidirectional"))
    )
    (net (code "167") (name "unconnected-(IC8-DISABLE-Pad8)") (class "Default")
      (node (ref "IC8") (pin "8") (pinfunction "DISABLE_8") (pintype "passive"))
    )
    (net (code "168") (name "unconnected-(IC9-N{slash}C-Pad4)") (class "Default")
      (node (ref "IC9") (pin "4") (pinfunction "N/C_4") (pintype "bidirectional"))
    )
    (net (code "169") (name "unconnected-(IC11-DISABLE-Pad8)") (class "Default")
      (node (ref "IC11") (pin "8") (pinfunction "DISABLE_8") (pintype "passive"))
    )
    (net (code "170") (name "unconnected-(J2-Pad8)") (class "Default")
      (node (ref "J2") (pin "8") (pinfunction "8_8") (pintype "passive"))
    )
    (net (code "171") (name "unconnected-(J3-Pad8)") (class "Default")
      (node (ref "J3") (pin "8") (pinfunction "8_8") (pintype "passive"))
    )
    (net (code "172") (name "unconnected-(J4-Pad8)") (class "Default")
      (node (ref "J4") (pin "8") (pinfunction "8_8") (pintype "passive"))
    )
    (net (code "173") (name "unconnected-(OSC1-STANDBY#-PadP$1)") (class "Default")
      (node (ref "OSC1") (pin "P$1") (pinfunction "STANDBY#_P$1") (pintype "passive"))
    )
    (net (code "174") (name "unconnected-(PDI-Pad3)") (class "Default")
      (node (ref "PDI") (pin "3") (pinfunction "3_3") (pintype "passive"))
    )
    (net (code "175") (name "unconnected-(PDI-Pad4)") (class "Default")
      (node (ref "PDI") (pin "4") (pinfunction "4_4") (pintype "passive"))
    )
    (net (code "176") (name "unconnected-(USB-4-PadP$4)") (class "Default")
      (node (ref "USB") (pin "P$4") (pinfunction "4_P$4") (pintype "bidirectional"))
    )
    (net (code "177") (name "unconnected-(USB-P$2-PadSHIELD_2)") (class "Default")
      (node (ref "USB") (pin "SHIELD_2") (pinfunction "P$2_SHIELD_2") (pintype "bidirectional"))
    )
    (net (code "178") (name "unconnected-(USB-P$3-PadSHIELD_3)") (class "Default")
      (node (ref "USB") (pin "SHIELD_3") (pinfunction "P$3_SHIELD_3") (pintype "bidirectional"))
    )
  )
)
